# InkTime.net
KiCad netlist of a schematic drawn in EAGLE
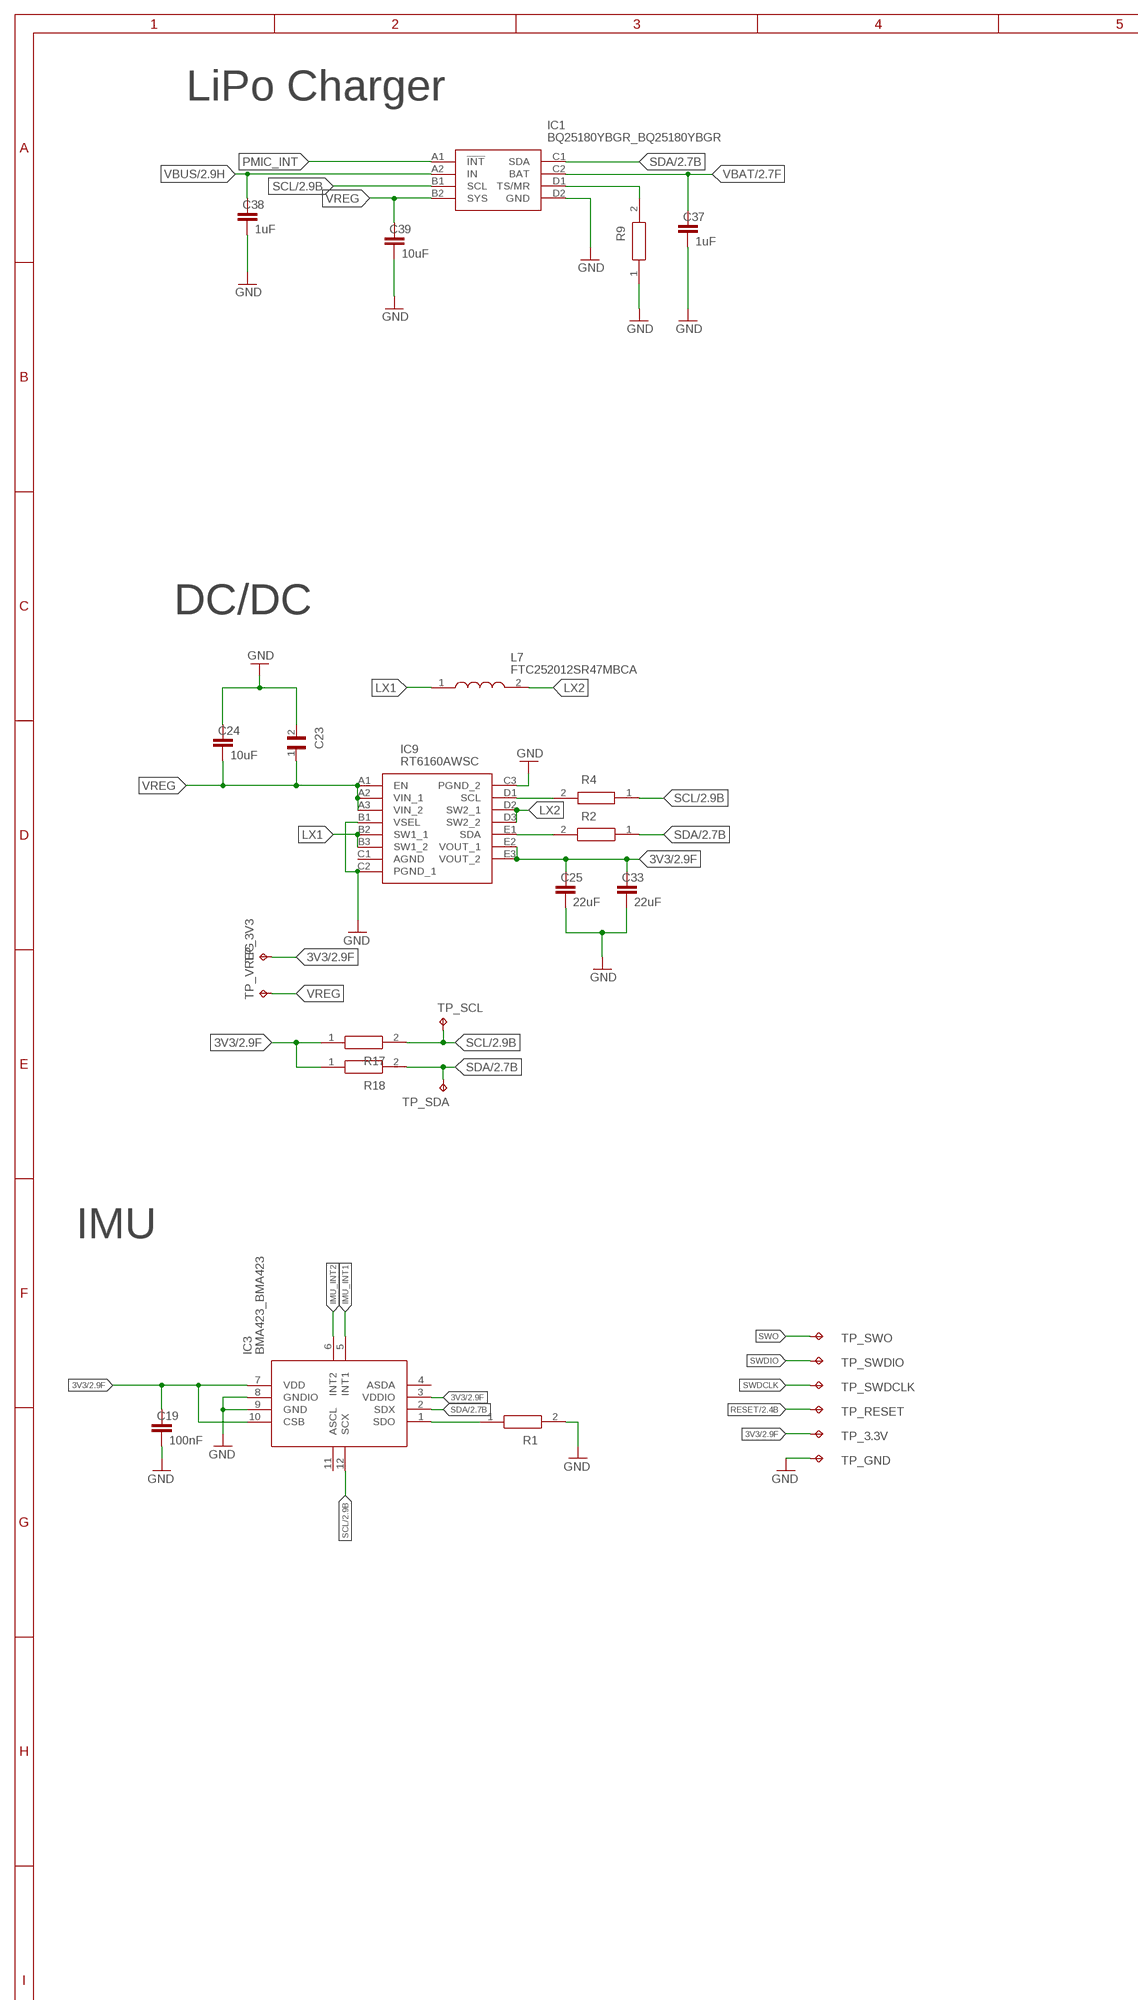
[diagram p0: schematic, sheet 1, part 1 of 2]
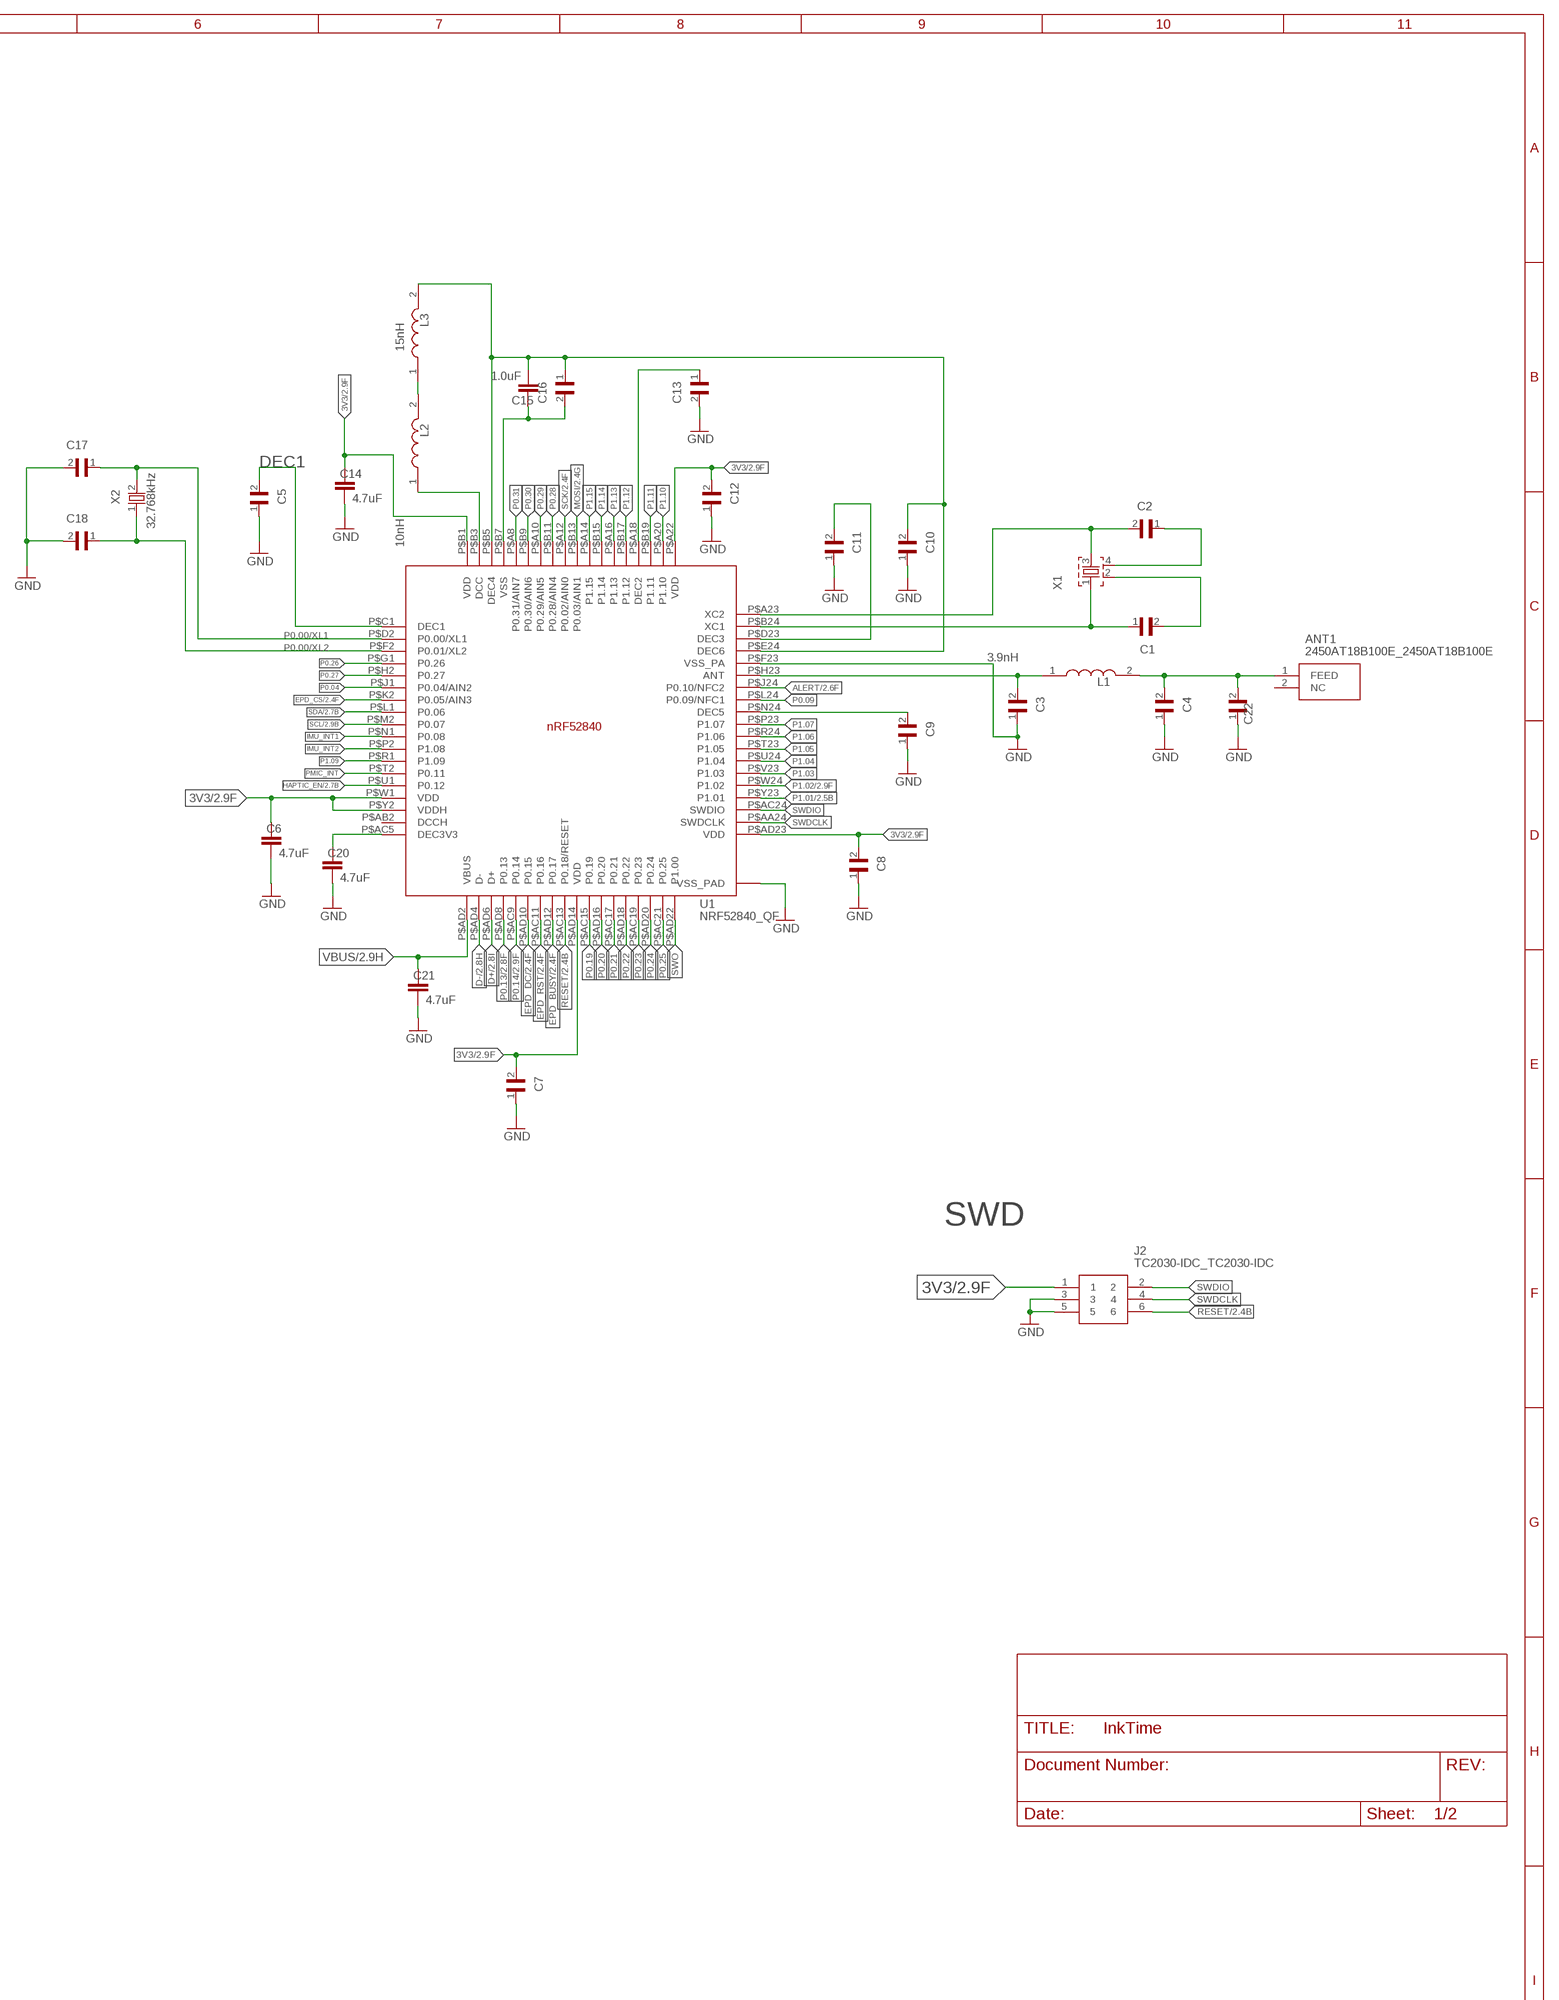
[diagram p1: schematic, sheet 1, part 2 of 2]
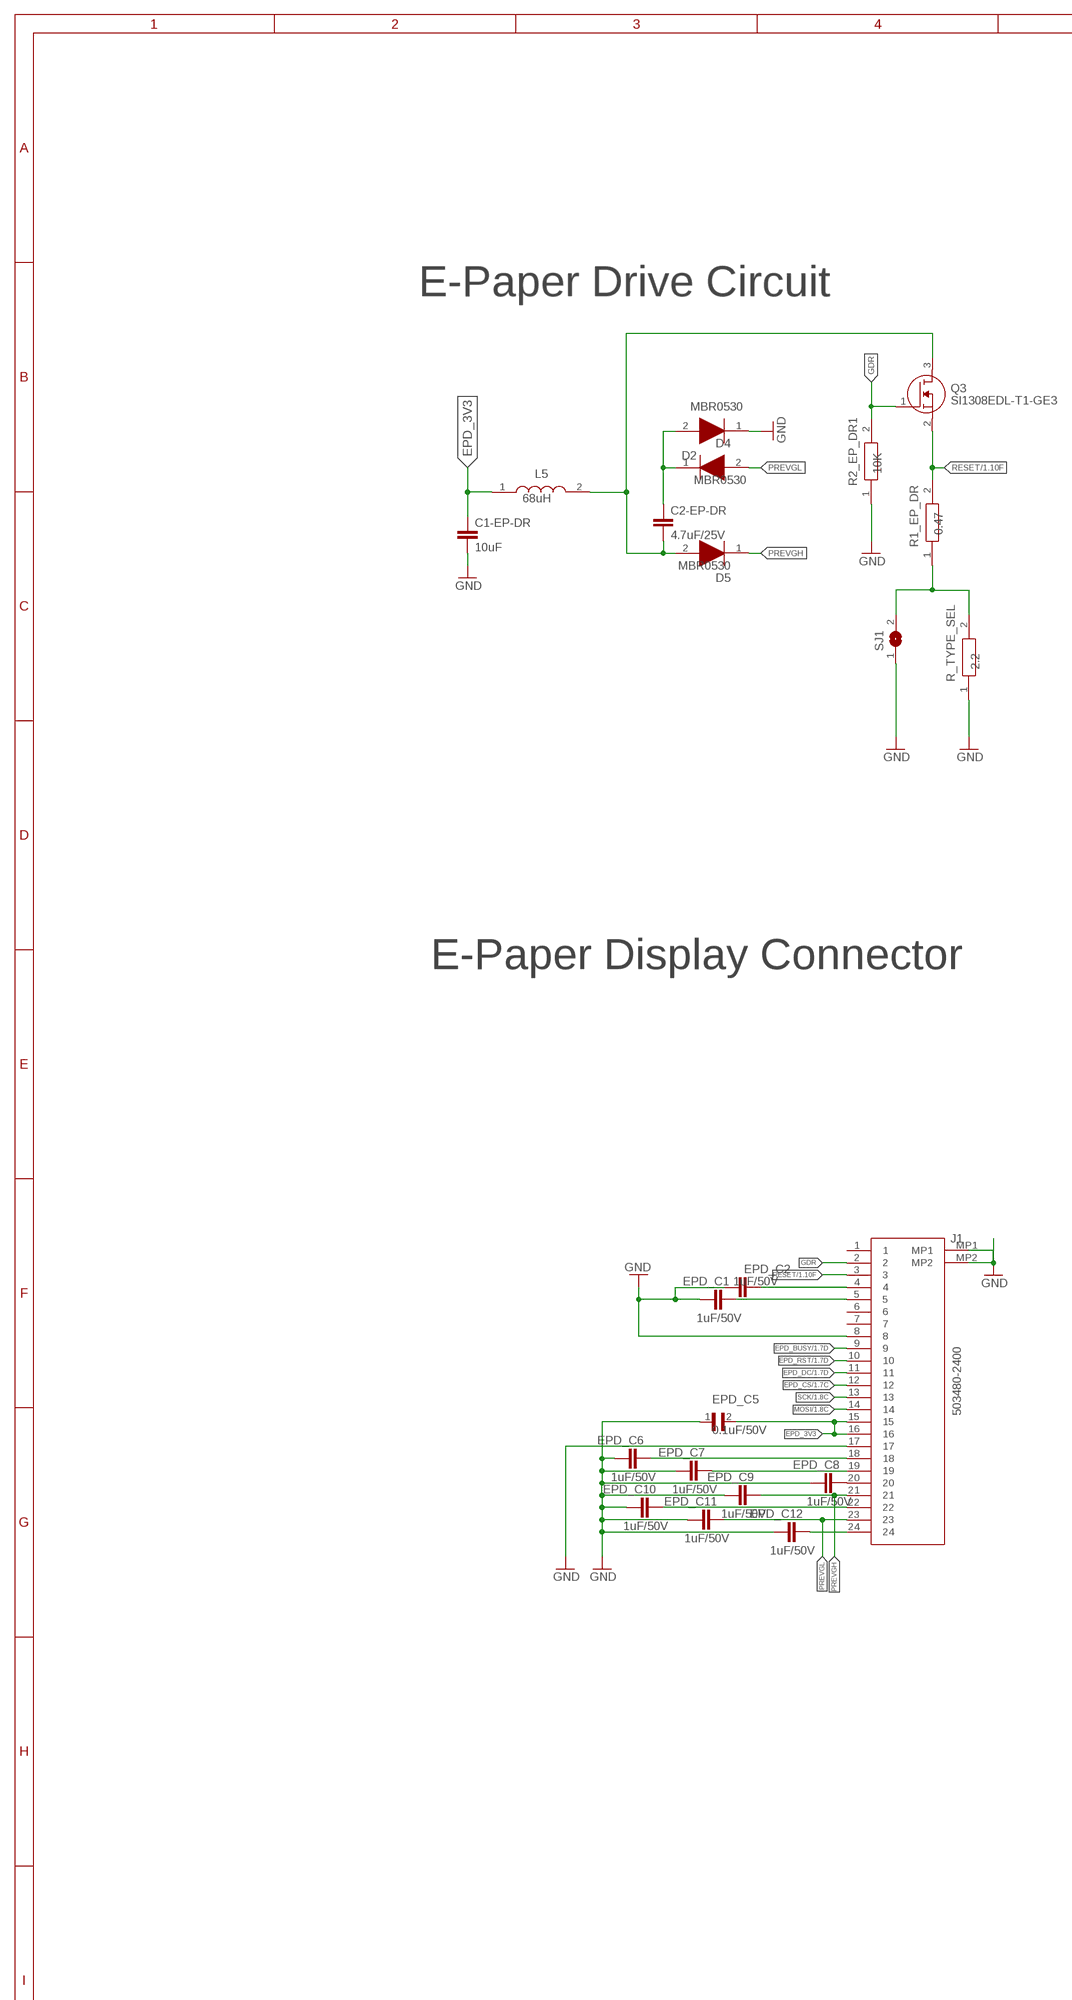
[diagram p2: schematic, sheet 2, part 1 of 2]
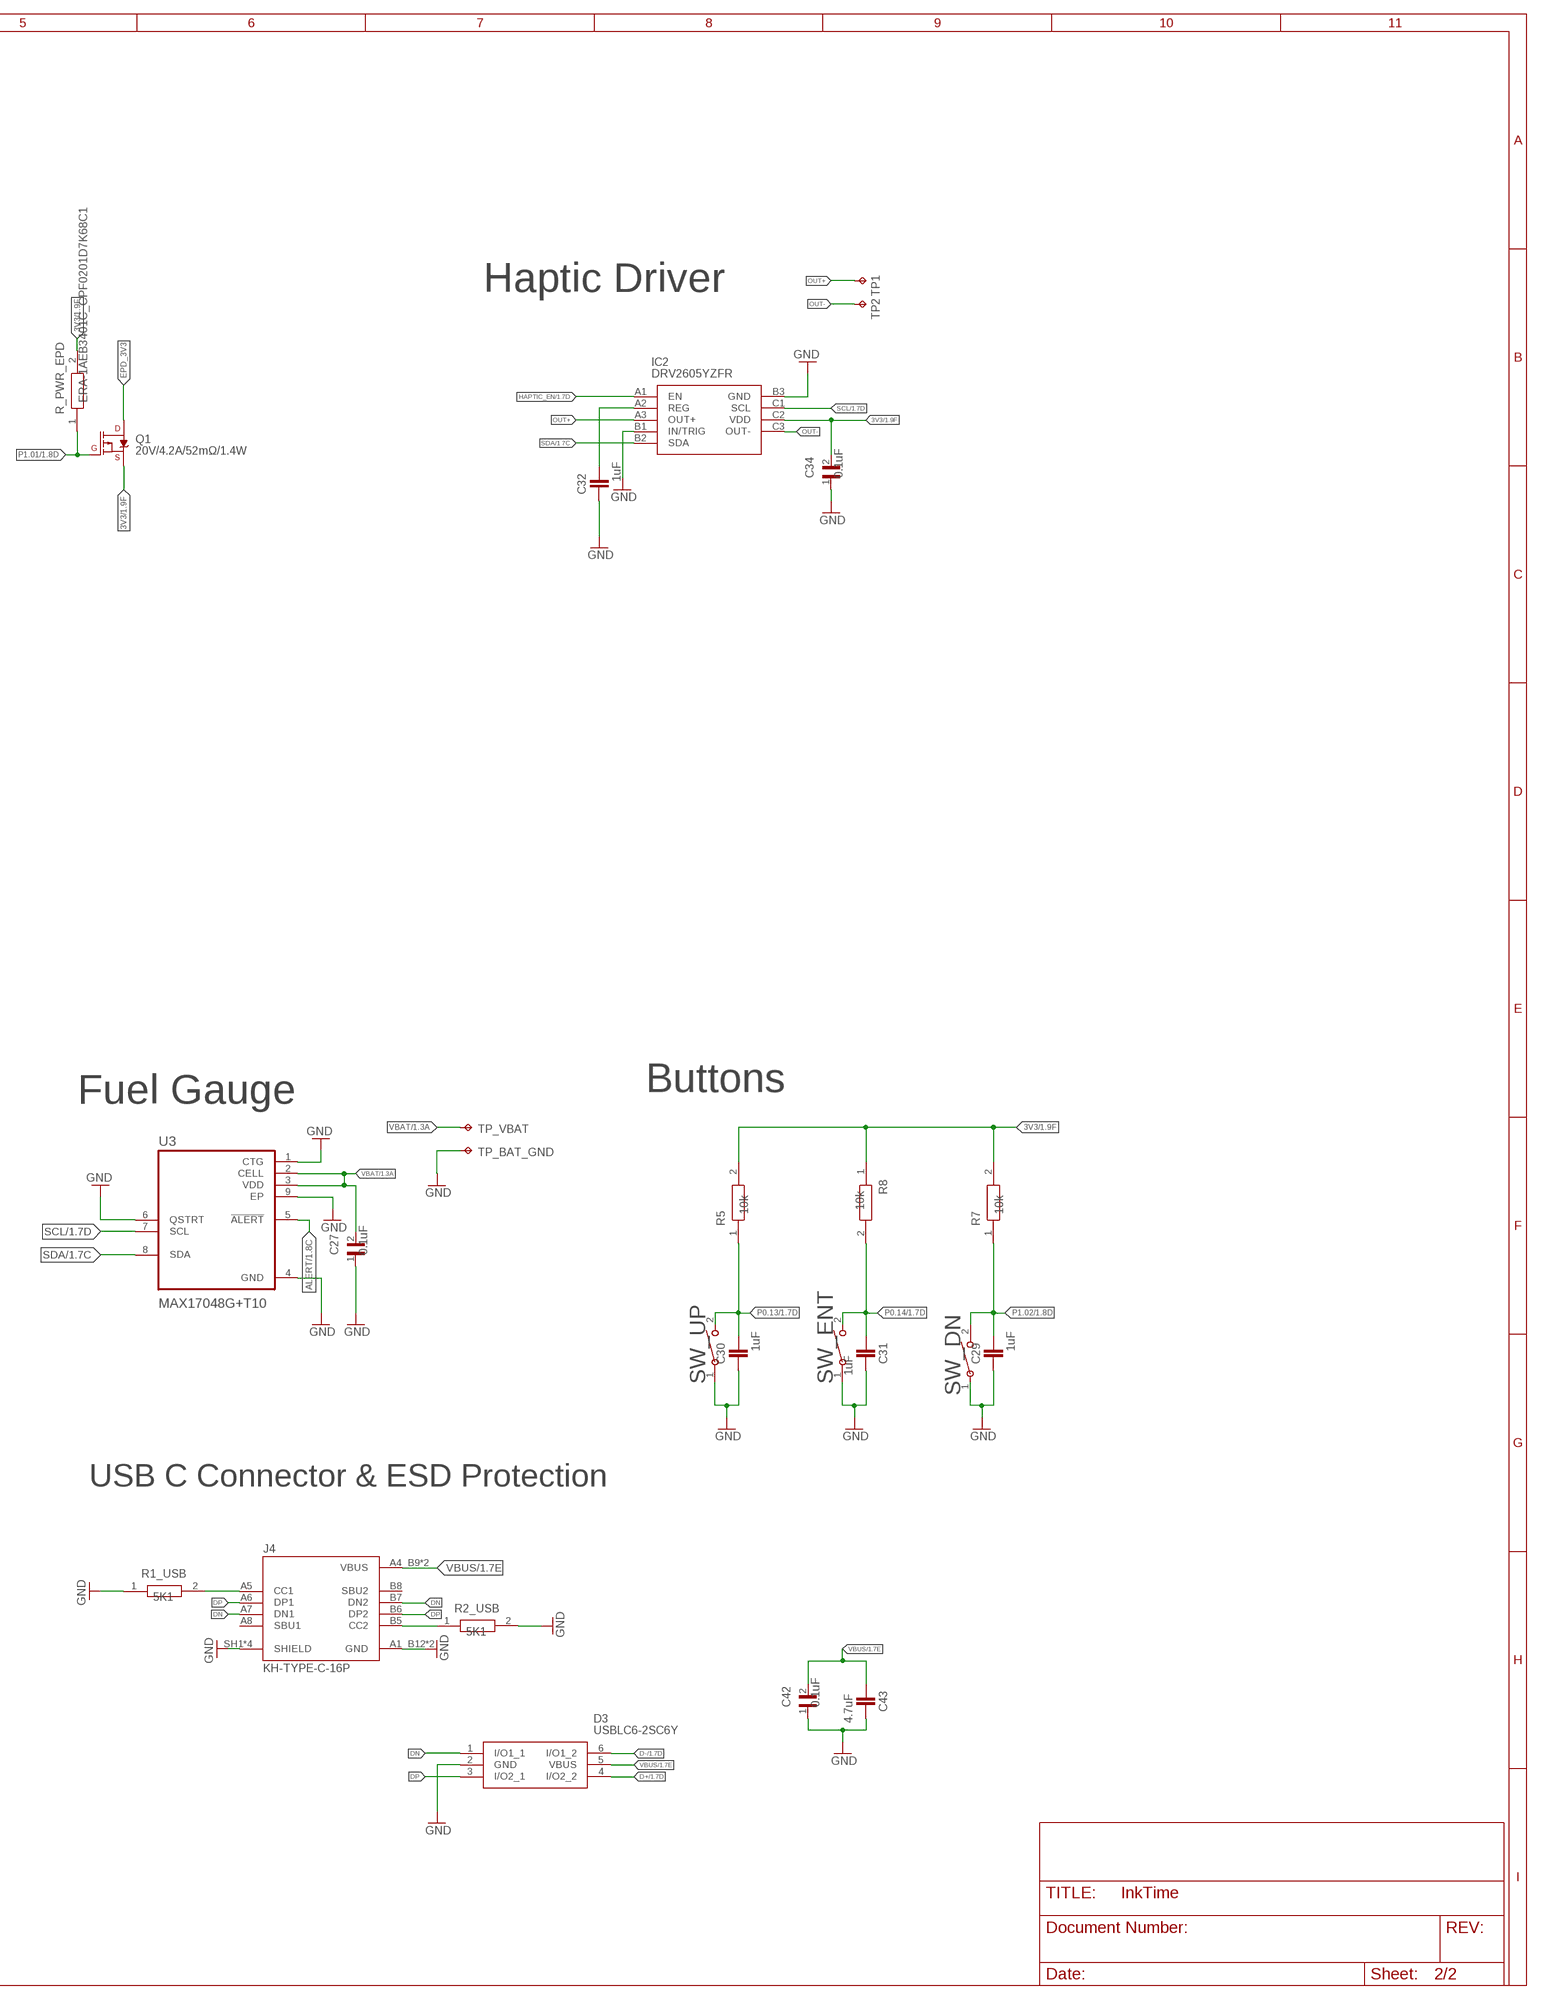
[diagram p3: schematic, sheet 2, part 2 of 2]

(export (version "E")
  (design (tool "Eeschema 10.0.6"))
  (components
    (comp (ref "C1-EP-DR")
      (value "10uF")
      (footprint "eagle-import:NORDIC_NRF_3_RESC0402_N")
      (libsource (lib "eagle-import") (part "NORDIC_NRF_3_CAPACITOR_0402_N"))
    )
    (comp (ref "C2-EP-DR")
      (value "4.7uF/25V")
      (footprint "eagle-import:NORDIC_NRF_3_RESC0402_N")
      (libsource (lib "eagle-import") (part "NORDIC_NRF_3_CAPACITOR_0402_N"))
    )
    (comp (ref "C27")
      (value "0.1uF")
      (footprint "eagle-import:GRM011R60J152KE01L_2_CAPC0201X13N")
      (fields (field (name "MF") "Murata") (field (name "MP") "GRM011R60J152KE01L"))
      (libsource (lib "eagle-import") (part "GRM011R60J152KE01L_2_GRM011R60J152KE01L"))
    )
    (comp (ref "C29")
      (value "1uF")
      (footprint "eagle-import:NORDIC_NRF_3_RESC0402_N")
      (libsource (lib "eagle-import") (part "NORDIC_NRF_3_CAPACITOR_0402_N"))
    )
    (comp (ref "C30")
      (value "1uF")
      (footprint "eagle-import:NORDIC_NRF_3_RESC0402_N")
      (libsource (lib "eagle-import") (part "NORDIC_NRF_3_CAPACITOR_0402_N"))
    )
    (comp (ref "C31")
      (value "1uF")
      (footprint "eagle-import:NORDIC_NRF_3_RESC0402_N")
      (libsource (lib "eagle-import") (part "NORDIC_NRF_3_CAPACITOR_0402_N"))
    )
    (comp (ref "C32")
      (value "1uF")
      (footprint "eagle-import:NORDIC_NRF_3_RESC0402_N")
      (libsource (lib "eagle-import") (part "NORDIC_NRF_3_CAPACITOR_0402_N"))
    )
    (comp (ref "C34")
      (value "0.1uF")
      (footprint "eagle-import:GRM011R60J152KE01L_2_CAPC0201X13N")
      (fields (field (name "MF") "Murata") (field (name "MP") "GRM011R60J152KE01L"))
      (libsource (lib "eagle-import") (part "GRM011R60J152KE01L_2_GRM011R60J152KE01L"))
    )
    (comp (ref "C42")
      (value "0.1uF")
      (footprint "eagle-import:GRM011R60J152KE01L_2_CAPC0201X13N")
      (fields (field (name "MF") "Murata") (field (name "MP") "GRM011R60J152KE01L"))
      (libsource (lib "eagle-import") (part "GRM011R60J152KE01L_2_GRM011R60J152KE01L"))
    )
    (comp (ref "C43")
      (value "4.7uF")
      (footprint "eagle-import:NORDIC_NRF_3_RESC0402_N")
      (libsource (lib "eagle-import") (part "NORDIC_NRF_3_CAPACITOR_0402_N"))
    )
    (comp (ref "D2")
      (value "MBR0530")
      (footprint "eagle-import:ESP32_C6_LIBRARY_5_SOD3716X135N")
      (fields (field (name "MF") "ON Semiconductor"))
      (libsource (lib "eagle-import") (part "ESP32_C6_LIBRARY_5_MBR0530"))
    )
    (comp (ref "D3")
      (value "USBLC6-2SC6Y")
      (footprint "eagle-import:ESP32_C6_LIBRARY_3_SOT95P280X145-6N")
      (fields (field (name "MF") "STMicroelectronics"))
      (libsource (lib "eagle-import") (part "ESP32_C6_LIBRARY_3_USBLC6-2SC6Y"))
    )
    (comp (ref "D4")
      (value "MBR0530")
      (footprint "eagle-import:ESP32_C6_LIBRARY_5_SOD3716X135N")
      (fields (field (name "MF") "ON Semiconductor"))
      (libsource (lib "eagle-import") (part "ESP32_C6_LIBRARY_5_MBR0530"))
    )
    (comp (ref "D5")
      (value "MBR0530")
      (footprint "eagle-import:ESP32_C6_LIBRARY_5_SOD3716X135N")
      (fields (field (name "MF") "ON Semiconductor"))
      (libsource (lib "eagle-import") (part "ESP32_C6_LIBRARY_5_MBR0530"))
    )
    (comp (ref "EPD_C1")
      (value "1uF/50V")
      (footprint "eagle-import:NORDIC_NRF_3_RESC0402_N")
      (libsource (lib "eagle-import") (part "NORDIC_NRF_3_CAPACITOR_0402_N"))
    )
    (comp (ref "EPD_C2")
      (value "1uF/50V")
      (footprint "eagle-import:NORDIC_NRF_3_RESC0402_N")
      (libsource (lib "eagle-import") (part "NORDIC_NRF_3_CAPACITOR_0402_N"))
    )
    (comp (ref "EPD_C5")
      (value "0.1uF/50V")
      (footprint "eagle-import:GRM011R60J152KE01L_2_CAPC0201X13N")
      (fields (field (name "MF") "Murata") (field (name "MP") "GRM011R60J152KE01L"))
      (libsource (lib "eagle-import") (part "GRM011R60J152KE01L_2_GRM011R60J152KE01L"))
    )
    (comp (ref "EPD_C6")
      (value "1uF/50V")
      (footprint "eagle-import:NORDIC_NRF_3_RESC0402_N")
      (libsource (lib "eagle-import") (part "NORDIC_NRF_3_CAPACITOR_0402_N"))
    )
    (comp (ref "EPD_C7")
      (value "1uF/50V")
      (footprint "eagle-import:NORDIC_NRF_3_RESC0402_N")
      (libsource (lib "eagle-import") (part "NORDIC_NRF_3_CAPACITOR_0402_N"))
    )
    (comp (ref "EPD_C8")
      (value "1uF/50V")
      (footprint "eagle-import:NORDIC_NRF_3_RESC0402_N")
      (libsource (lib "eagle-import") (part "NORDIC_NRF_3_CAPACITOR_0402_N"))
    )
    (comp (ref "EPD_C9")
      (value "1uF/50V")
      (footprint "eagle-import:NORDIC_NRF_3_RESC0402_N")
      (libsource (lib "eagle-import") (part "NORDIC_NRF_3_CAPACITOR_0402_N"))
    )
    (comp (ref "EPD_C10")
      (value "1uF/50V")
      (footprint "eagle-import:NORDIC_NRF_3_RESC0402_N")
      (libsource (lib "eagle-import") (part "NORDIC_NRF_3_CAPACITOR_0402_N"))
    )
    (comp (ref "EPD_C11")
      (value "1uF/50V")
      (footprint "eagle-import:NORDIC_NRF_3_RESC0402_N")
      (libsource (lib "eagle-import") (part "NORDIC_NRF_3_CAPACITOR_0402_N"))
    )
    (comp (ref "EPD_C12")
      (value "1uF/50V")
      (footprint "eagle-import:NORDIC_NRF_3_RESC0402_N")
      (libsource (lib "eagle-import") (part "NORDIC_NRF_3_CAPACITOR_0402_N"))
    )
    (comp (ref "IC2")
      (value "DRV2605YZFR")
      (footprint "eagle-import:DRV2605YZFR_BGA9C50P3X3_144X144X62")
      (libsource (lib "eagle-import") (part "DRV2605YZFR_DRV2605YZFR"))
    )
    (comp (ref "J1")
      (value "503480-2400")
      (footprint "eagle-import:503480-2400_5034802400")
      (fields (field (name "MOUSER_PART_NUMBER") "538-503480-2400"))
      (libsource (lib "eagle-import") (part "503480-2400_503480-2400"))
    )
    (comp (ref "J4")
      (value "KH-TYPE-C-16P")
      (footprint "eagle-import:KH-TYPE-C-16P_KINGHELM_KH-TYPE-C-16P")
      (fields (field (name "MF") "kinghelm"))
      (libsource (lib "eagle-import") (part "KH-TYPE-C-16P_KH-TYPE-C-16P"))
    )
    (comp (ref "L5")
      (value "68uH")
      (footprint "eagle-import:MLP2016SR47MT0S1_INDC2016X100N")
      (fields (field (name "MANUFACTURER_PART_NUMBER") "FTC252012SR47MBCA"))
      (libsource (lib "eagle-import") (part "MLP2016SR47MT0S1_FTC252012SR47MBCA"))
    )
    (comp (ref "Q1")
      (value "20V/4.2A/52mΩ/1.4W")
      (footprint "eagle-import:ESP32_C6_LIBRARY_4_ESP32_C6_LIBRARY_4_ESP32_C6_LIBRARY_4_ESP32_C6_LIBRARY_4_ESP32_WROVER_SPARKFUN-DISCRETESEMI_SOT23-3")
      (libsource (lib "eagle-import") (part "ESP32_C6_LIBRARY_4_ESP32_WROVER_SPARKFUN-DISCRETESEMI_MOSFET_PCH-DMG2305UX-7"))
    )
    (comp (ref "Q3")
      (value "SI1308EDL-T1-GE3")
      (footprint "eagle-import:ESP32_C6_LIBRARY_6_SOT65P210X110-3N")
      (fields (field (name "MF") "Vishay Siliconix"))
      (libsource (lib "eagle-import") (part "ESP32_C6_LIBRARY_6_SI1308EDL-T1-GE3"))
    )
    (comp (ref "R1_EP_DR")
      (value "0.47")
      (footprint "eagle-import:ERA-1AEB3401C_0201")
      (libsource (lib "eagle-import") (part "ERA-1AEB3401C_CPF0201D7K68C1"))
    )
    (comp (ref "R1_USB")
      (value "5K1")
      (footprint "eagle-import:ERA-1AEB3401C_0201")
      (libsource (lib "eagle-import") (part "ERA-1AEB3401C_CPF0201D7K68C1"))
    )
    (comp (ref "R2_EP_DR1")
      (value "10K")
      (footprint "eagle-import:ERA-1AEB3401C_0201")
      (libsource (lib "eagle-import") (part "ERA-1AEB3401C_CPF0201D7K68C1"))
    )
    (comp (ref "R2_USB")
      (value "5K1")
      (footprint "eagle-import:ERA-1AEB3401C_0201")
      (libsource (lib "eagle-import") (part "ERA-1AEB3401C_CPF0201D7K68C1"))
    )
    (comp (ref "R5")
      (value "10k")
      (footprint "eagle-import:ERA-1AEB3401C_0201")
      (libsource (lib "eagle-import") (part "ERA-1AEB3401C_CPF0201D7K68C1"))
    )
    (comp (ref "R7")
      (value "10k")
      (footprint "eagle-import:ERA-1AEB3401C_0201")
      (libsource (lib "eagle-import") (part "ERA-1AEB3401C_CPF0201D7K68C1"))
    )
    (comp (ref "R8")
      (value "10k")
      (footprint "eagle-import:ERA-1AEB3401C_0201")
      (libsource (lib "eagle-import") (part "ERA-1AEB3401C_CPF0201D7K68C1"))
    )
    (comp (ref "R_PWR_EPD")
      (value "ERA-1AEB3401C_CPF0201D7K68C1")
      (footprint "eagle-import:ERA-1AEB3401C_0201")
      (libsource (lib "eagle-import") (part "ERA-1AEB3401C_CPF0201D7K68C1"))
    )
    (comp (ref "R_TYPE_SEL")
      (value "2.2")
      (footprint "eagle-import:ERA-1AEB3401C_0201")
      (libsource (lib "eagle-import") (part "ERA-1AEB3401C_CPF0201D7K68C1"))
    )
    (comp (ref "SJ1")
      (value "ESP32_C6_LIBRARY_7_JUMPER_SJ")
      (footprint "eagle-import:ESP32_C6_LIBRARY_7_JUMPER_SJ")
      (libsource (lib "eagle-import") (part "ESP32_C6_LIBRARY_7_JUMPER_SJ"))
    )
    (comp (ref "SW_DN")
      (value "2025-10-22_07-23-44_LIBRARY_EVP-AKE31ASW_EVP-AKE31A_PAN")
      (footprint "eagle-import:2025-10-22_07-23-44_LIBRARY_SW_EVP-AKE31A_PAN")
      (fields
        (field (name "MANUFACTURER_PART_NUMBER") "EVP-AKE31A")
        (field (name "COPYRIGHT") "Copyright (C) 2025 Ultra Librarian. All rights reserved.")
      )
      (libsource (lib "eagle-import") (part "2025-10-22_07-23-44_LIBRARY_EVP-AKE31ASW_EVP-AKE31A_PAN"))
    )
    (comp (ref "SW_ENT")
      (value "2025-10-22_07-23-44_LIBRARY_EVP-AKE31ASW_EVP-AKE31A_PAN")
      (footprint "eagle-import:2025-10-22_07-23-44_LIBRARY_SW_EVP-AKE31A_PAN")
      (fields
        (field (name "MANUFACTURER_PART_NUMBER") "EVP-AKE31A")
        (field (name "COPYRIGHT") "Copyright (C) 2025 Ultra Librarian. All rights reserved.")
      )
      (libsource (lib "eagle-import") (part "2025-10-22_07-23-44_LIBRARY_EVP-AKE31ASW_EVP-AKE31A_PAN"))
    )
    (comp (ref "SW_UP")
      (value "2025-10-22_07-23-44_LIBRARY_EVP-AKE31ASW_EVP-AKE31A_PAN")
      (footprint "eagle-import:2025-10-22_07-23-44_LIBRARY_SW_EVP-AKE31A_PAN")
      (fields
        (field (name "MANUFACTURER_PART_NUMBER") "EVP-AKE31A")
        (field (name "COPYRIGHT") "Copyright (C) 2025 Ultra Librarian. All rights reserved.")
      )
      (libsource (lib "eagle-import") (part "2025-10-22_07-23-44_LIBRARY_EVP-AKE31ASW_EVP-AKE31A_PAN"))
    )
    (comp (ref "TP1")
      (value "HECTOR_WATCH_1_TPTP20R")
      (footprint "eagle-import:HECTOR_WATCH_1_TP20R")
      (libsource (lib "eagle-import") (part "HECTOR_WATCH_1_TPTP20R"))
    )
    (comp (ref "TP2")
      (value "HECTOR_WATCH_1_TPTP20R")
      (footprint "eagle-import:HECTOR_WATCH_1_TP20R")
      (libsource (lib "eagle-import") (part "HECTOR_WATCH_1_TPTP20R"))
    )
    (comp (ref "TP_BAT_GND")
      (value "HECTOR_WATCH_1_TPTP20R")
      (footprint "eagle-import:HECTOR_WATCH_1_TP20R")
      (libsource (lib "eagle-import") (part "HECTOR_WATCH_1_TPTP20R"))
    )
    (comp (ref "TP_VBAT")
      (value "HECTOR_WATCH_1_TPTP20R")
      (footprint "eagle-import:HECTOR_WATCH_1_TP20R")
      (libsource (lib "eagle-import") (part "HECTOR_WATCH_1_TPTP20R"))
    )
    (comp (ref "U3")
      (value "MAX17048G+T10")
      (footprint "eagle-import:ESP32_C6_LIBRARY_SON50P200X200X80-9N")
      (fields (field (name "MF") "Analog Devices"))
      (libsource (lib "eagle-import") (part "ESP32_C6_LIBRARY_MAX17048G+T10"))
    )
    (comp (ref "ANT1")
      (value "2450AT18B100E_2450AT18B100E")
      (footprint "eagle-import:2450AT18B100E_ANTC3216X140N")
      (fields
        (field (name "ARROW_PART_NUMBER") "2450AT18B100E")
        (field (name "MOUSER_PART_NUMBER") "609-2450AT18B100E")
      )
      (libsource (lib "eagle-import") (part "2450AT18B100E_2450AT18B100E"))
    )
    (comp (ref "C1")
      (value "12pF")
      (footprint "eagle-import:GRM011R60J152KE01L_2_CAPC0201X13N")
      (fields (field (name "MF") "Murata") (field (name "MP") "GRM011R60J152KE01L"))
      (libsource (lib "eagle-import") (part "GRM011R60J152KE01L_2_GRM011R60J152KE01L"))
    )
    (comp (ref "C2")
      (value "12pF")
      (footprint "eagle-import:GRM011R60J152KE01L_2_CAPC0201X13N")
      (fields (field (name "MF") "Murata") (field (name "MP") "GRM011R60J152KE01L"))
      (libsource (lib "eagle-import") (part "GRM011R60J152KE01L_2_GRM011R60J152KE01L"))
    )
    (comp (ref "C3")
      (value "1pF")
      (footprint "eagle-import:GRM011R60J152KE01L_2_CAPC0201X13N")
      (fields (field (name "MF") "Murata") (field (name "MP") "GRM011R60J152KE01L"))
      (libsource (lib "eagle-import") (part "GRM011R60J152KE01L_2_GRM011R60J152KE01L"))
    )
    (comp (ref "C4")
      (value "1pF")
      (footprint "eagle-import:GRM011R60J152KE01L_2_CAPC0201X13N")
      (fields (field (name "MF") "Murata") (field (name "MP") "GRM011R60J152KE01L"))
      (libsource (lib "eagle-import") (part "GRM011R60J152KE01L_2_GRM011R60J152KE01L"))
    )
    (comp (ref "C5")
      (value "100nF")
      (footprint "eagle-import:GRM011R60J152KE01L_2_CAPC0201X13N")
      (fields (field (name "MF") "Murata") (field (name "MP") "GRM011R60J152KE01L"))
      (libsource (lib "eagle-import") (part "GRM011R60J152KE01L_2_GRM011R60J152KE01L"))
    )
    (comp (ref "C6")
      (value "4.7uF")
      (footprint "eagle-import:NORDIC_NRF_3_RESC0402_N")
      (libsource (lib "eagle-import") (part "NORDIC_NRF_3_CAPACITOR_0402_N"))
    )
    (comp (ref "C7")
      (value "100nF")
      (footprint "eagle-import:GRM011R60J152KE01L_2_CAPC0201X13N")
      (fields (field (name "MF") "Murata") (field (name "MP") "GRM011R60J152KE01L"))
      (libsource (lib "eagle-import") (part "GRM011R60J152KE01L_2_GRM011R60J152KE01L"))
    )
    (comp (ref "C8")
      (value "100nF")
      (footprint "eagle-import:GRM011R60J152KE01L_2_CAPC0201X13N")
      (fields (field (name "MF") "Murata") (field (name "MP") "GRM011R60J152KE01L"))
      (libsource (lib "eagle-import") (part "GRM011R60J152KE01L_2_GRM011R60J152KE01L"))
    )
    (comp (ref "C9")
      (value "820pF")
      (footprint "eagle-import:GRM011R60J152KE01L_2_CAPC0201X13N")
      (fields (field (name "MF") "Murata") (field (name "MP") "GRM011R60J152KE01L"))
      (libsource (lib "eagle-import") (part "GRM011R60J152KE01L_2_GRM011R60J152KE01L"))
    )
    (comp (ref "C10")
      (value "N.C.")
      (footprint "eagle-import:GRM011R60J152KE01L_2_CAPC0201X13N")
      (fields (field (name "MF") "Murata") (field (name "MP") "GRM011R60J152KE01L"))
      (libsource (lib "eagle-import") (part "GRM011R60J152KE01L_2_GRM011R60J152KE01L"))
    )
    (comp (ref "C11")
      (value "100pF")
      (footprint "eagle-import:GRM011R60J152KE01L_2_CAPC0201X13N")
      (fields (field (name "MF") "Murata") (field (name "MP") "GRM011R60J152KE01L"))
      (libsource (lib "eagle-import") (part "GRM011R60J152KE01L_2_GRM011R60J152KE01L"))
    )
    (comp (ref "C12")
      (value "100nF")
      (footprint "eagle-import:GRM011R60J152KE01L_2_CAPC0201X13N")
      (fields (field (name "MF") "Murata") (field (name "MP") "GRM011R60J152KE01L"))
      (libsource (lib "eagle-import") (part "GRM011R60J152KE01L_2_GRM011R60J152KE01L"))
    )
    (comp (ref "C13")
      (value "N.C.")
      (footprint "eagle-import:GRM011R60J152KE01L_2_CAPC0201X13N")
      (fields (field (name "MF") "Murata") (field (name "MP") "GRM011R60J152KE01L"))
      (libsource (lib "eagle-import") (part "GRM011R60J152KE01L_2_GRM011R60J152KE01L"))
    )
    (comp (ref "C14")
      (value "4.7uF")
      (footprint "eagle-import:NORDIC_NRF_3_RESC0402_N")
      (libsource (lib "eagle-import") (part "NORDIC_NRF_3_CAPACITOR_0402_N"))
    )
    (comp (ref "C15")
      (value "1.0uF")
      (footprint "eagle-import:NORDIC_NRF_3_RESC0402_N")
      (libsource (lib "eagle-import") (part "NORDIC_NRF_3_CAPACITOR_0402_N"))
    )
    (comp (ref "C16")
      (value "47nF")
      (footprint "eagle-import:GRM011R60J152KE01L_2_CAPC0201X13N")
      (fields (field (name "MF") "Murata") (field (name "MP") "GRM011R60J152KE01L"))
      (libsource (lib "eagle-import") (part "GRM011R60J152KE01L_2_GRM011R60J152KE01L"))
    )
    (comp (ref "C17")
      (value "12pF")
      (footprint "eagle-import:GRM011R60J152KE01L_2_CAPC0201X13N")
      (fields (field (name "MF") "Murata") (field (name "MP") "GRM011R60J152KE01L"))
      (libsource (lib "eagle-import") (part "GRM011R60J152KE01L_2_GRM011R60J152KE01L"))
    )
    (comp (ref "C18")
      (value "12pF")
      (footprint "eagle-import:GRM011R60J152KE01L_2_CAPC0201X13N")
      (fields (field (name "MF") "Murata") (field (name "MP") "GRM011R60J152KE01L"))
      (libsource (lib "eagle-import") (part "GRM011R60J152KE01L_2_GRM011R60J152KE01L"))
    )
    (comp (ref "C19")
      (value "100nF")
      (footprint "eagle-import:NORDIC_NRF_3_RESC0402_N")
      (libsource (lib "eagle-import") (part "NORDIC_NRF_3_CAPACITOR_0402_N"))
    )
    (comp (ref "C20")
      (value "4.7uF")
      (footprint "eagle-import:NORDIC_NRF_3_RESC0402_N")
      (libsource (lib "eagle-import") (part "NORDIC_NRF_3_CAPACITOR_0402_N"))
    )
    (comp (ref "C21")
      (value "4.7uF")
      (footprint "eagle-import:NORDIC_NRF_3_RESC0402_N")
      (libsource (lib "eagle-import") (part "NORDIC_NRF_3_CAPACITOR_0402_N"))
    )
    (comp (ref "C22")
      (value "N.C.")
      (footprint "eagle-import:GRM011R60J152KE01L_2_CAPC0201X13N")
      (fields (field (name "MF") "Murata") (field (name "MP") "GRM011R60J152KE01L"))
      (libsource (lib "eagle-import") (part "GRM011R60J152KE01L_2_GRM011R60J152KE01L"))
    )
    (comp (ref "C23")
      (value "0.1uF")
      (footprint "eagle-import:GRM011R60J152KE01L_2_CAPC0201X13N")
      (fields (field (name "MF") "Murata") (field (name "MP") "GRM011R60J152KE01L"))
      (libsource (lib "eagle-import") (part "GRM011R60J152KE01L_2_GRM011R60J152KE01L"))
    )
    (comp (ref "C24")
      (value "10uF")
      (footprint "eagle-import:NORDIC_NRF_3_RESC0402_N")
      (libsource (lib "eagle-import") (part "NORDIC_NRF_3_CAPACITOR_0402_N"))
    )
    (comp (ref "C25")
      (value "22uF")
      (footprint "eagle-import:NORDIC_NRF_3_RESC0402_N")
      (libsource (lib "eagle-import") (part "NORDIC_NRF_3_CAPACITOR_0402_N"))
    )
    (comp (ref "C33")
      (value "22uF")
      (footprint "eagle-import:NORDIC_NRF_3_RESC0402_N")
      (libsource (lib "eagle-import") (part "NORDIC_NRF_3_CAPACITOR_0402_N"))
    )
    (comp (ref "C37")
      (value "1uF")
      (footprint "eagle-import:NORDIC_NRF_3_RESC0402_N")
      (libsource (lib "eagle-import") (part "NORDIC_NRF_3_CAPACITOR_0402_N"))
    )
    (comp (ref "C38")
      (value "1uF")
      (footprint "eagle-import:NORDIC_NRF_3_RESC0402_N")
      (libsource (lib "eagle-import") (part "NORDIC_NRF_3_CAPACITOR_0402_N"))
    )
    (comp (ref "C39")
      (value "10uF")
      (footprint "eagle-import:NORDIC_NRF_3_RESC0402_N")
      (libsource (lib "eagle-import") (part "NORDIC_NRF_3_CAPACITOR_0402_N"))
    )
    (comp (ref "IC1")
      (value "BQ25180YBGR_BQ25180YBGR")
      (footprint "eagle-import:BQ25180YBGR_BGA8C40P2X4_100X155X50")
      (fields
        (field (name "ARROW_PART_NUMBER") "BQ25180YBGR")
        (field (name "MOUSER_PART_NUMBER") "595-BQ25180YBGR")
      )
      (libsource (lib "eagle-import") (part "BQ25180YBGR_BQ25180YBGR"))
    )
    (comp (ref "IC3")
      (value "BMA423_BMA423")
      (footprint "eagle-import:BMA423_BMA423")
      (fields (field (name "ARROW_PART_NUMBER") "BMA423") (field (name "MOUSER_PART_NUMBER") "262-BMA423"))
      (libsource (lib "eagle-import") (part "BMA423_BMA423"))
    )
    (comp (ref "IC9")
      (value "RT6160AWSC")
      (footprint "eagle-import:RT6160AWSC_BGA15C40P3X5_140X230X60")
      (fields (field (name "MOUSER_PART_NUMBER") "835-RT6160AWSC"))
      (libsource (lib "eagle-import") (part "RT6160AWSC_RT6160AWSC"))
    )
    (comp (ref "J2")
      (value "TC2030-IDC_TC2030-IDC")
      (footprint "eagle-import:TC2030-IDC_TC2030IDC")
      (fields (field (name "MANUFACTURER_PART_NUMBER") "TC2030-IDC"))
      (libsource (lib "eagle-import") (part "TC2030-IDC_TC2030-IDC"))
    )
    (comp (ref "L1")
      (value "3.9nH")
      (footprint "eagle-import:MLP2016SR47MT0S1_INDC2016X100N")
      (fields (field (name "MANUFACTURER_PART_NUMBER") "FTC252012SR47MBCA"))
      (libsource (lib "eagle-import") (part "MLP2016SR47MT0S1_FTC252012SR47MBCA"))
    )
    (comp (ref "L2")
      (value "10nH")
      (footprint "eagle-import:MLP2016SR47MT0S1_INDC2016X100N")
      (fields (field (name "MANUFACTURER_PART_NUMBER") "FTC252012SR47MBCA"))
      (libsource (lib "eagle-import") (part "MLP2016SR47MT0S1_FTC252012SR47MBCA"))
    )
    (comp (ref "L3")
      (value "15nH")
      (footprint "eagle-import:MLP2016SR47MT0S1_INDC2016X100N")
      (fields (field (name "MANUFACTURER_PART_NUMBER") "FTC252012SR47MBCA"))
      (libsource (lib "eagle-import") (part "MLP2016SR47MT0S1_FTC252012SR47MBCA"))
    )
    (comp (ref "L7")
      (value "FTC252012SR47MBCA")
      (footprint "eagle-import:MLP2016SR47MT0S1_INDC2016X100N")
      (libsource (lib "eagle-import") (part "MLP2016SR47MT0S1_FTC252012SR47MBCA"))
    )
    (comp (ref "R1")
      (value "0")
      (footprint "eagle-import:ERA-1AEB3401C_0201")
      (libsource (lib "eagle-import") (part "ERA-1AEB3401C_CPF0201D7K68C1"))
    )
    (comp (ref "R2")
      (value "0")
      (footprint "eagle-import:ERA-1AEB3401C_0201")
      (libsource (lib "eagle-import") (part "ERA-1AEB3401C_CPF0201D7K68C1"))
    )
    (comp (ref "R4")
      (value "0")
      (footprint "eagle-import:ERA-1AEB3401C_0201")
      (libsource (lib "eagle-import") (part "ERA-1AEB3401C_CPF0201D7K68C1"))
    )
    (comp (ref "R9")
      (value "10k")
      (footprint "eagle-import:ERA-1AEB3401C_0201")
      (libsource (lib "eagle-import") (part "ERA-1AEB3401C_CPF0201D7K68C1"))
    )
    (comp (ref "R17")
      (value "3k3")
      (footprint "eagle-import:ERA-1AEB3401C_0201")
      (libsource (lib "eagle-import") (part "ERA-1AEB3401C_CPF0201D7K68C1"))
    )
    (comp (ref "R18")
      (value "3K3")
      (footprint "eagle-import:ERA-1AEB3401C_0201")
      (libsource (lib "eagle-import") (part "ERA-1AEB3401C_CPF0201D7K68C1"))
    )
    (comp (ref "TP_3.3V")
      (value "HECTOR_WATCH_1_TPTP20R")
      (footprint "eagle-import:HECTOR_WATCH_1_TP20R")
      (libsource (lib "eagle-import") (part "HECTOR_WATCH_1_TPTP20R"))
    )
    (comp (ref "TP_3V3")
      (value "HECTOR_WATCH_1_TPTP20R")
      (footprint "eagle-import:HECTOR_WATCH_1_TP20R")
      (libsource (lib "eagle-import") (part "HECTOR_WATCH_1_TPTP20R"))
    )
    (comp (ref "TP_GND")
      (value "HECTOR_WATCH_1_TPTP20R")
      (footprint "eagle-import:HECTOR_WATCH_1_TP20R")
      (libsource (lib "eagle-import") (part "HECTOR_WATCH_1_TPTP20R"))
    )
    (comp (ref "TP_RESET")
      (value "HECTOR_WATCH_1_TPTP20R")
      (footprint "eagle-import:HECTOR_WATCH_1_TP20R")
      (libsource (lib "eagle-import") (part "HECTOR_WATCH_1_TPTP20R"))
    )
    (comp (ref "TP_SCL")
      (value "HECTOR_WATCH_1_TPTP20R")
      (footprint "eagle-import:HECTOR_WATCH_1_TP20R")
      (libsource (lib "eagle-import") (part "HECTOR_WATCH_1_TPTP20R"))
    )
    (comp (ref "TP_SDA")
      (value "HECTOR_WATCH_1_TPTP20R")
      (footprint "eagle-import:HECTOR_WATCH_1_TP20R")
      (libsource (lib "eagle-import") (part "HECTOR_WATCH_1_TPTP20R"))
    )
    (comp (ref "TP_SWDCLK")
      (value "HECTOR_WATCH_1_TPTP20R")
      (footprint "eagle-import:HECTOR_WATCH_1_TP20R")
      (libsource (lib "eagle-import") (part "HECTOR_WATCH_1_TPTP20R"))
    )
    (comp (ref "TP_SWDIO")
      (value "HECTOR_WATCH_1_TPTP20R")
      (footprint "eagle-import:HECTOR_WATCH_1_TP20R")
      (libsource (lib "eagle-import") (part "HECTOR_WATCH_1_TPTP20R"))
    )
    (comp (ref "TP_SWO")
      (value "HECTOR_WATCH_1_TPTP20R")
      (footprint "eagle-import:HECTOR_WATCH_1_TP20R")
      (libsource (lib "eagle-import") (part "HECTOR_WATCH_1_TPTP20R"))
    )
    (comp (ref "TP_VREG")
      (value "HECTOR_WATCH_1_TPTP20R")
      (footprint "eagle-import:HECTOR_WATCH_1_TP20R")
      (libsource (lib "eagle-import") (part "HECTOR_WATCH_1_TPTP20R"))
    )
    (comp (ref "U1")
      (value "NRF52840_QF")
      (footprint "eagle-import:NORDIC_NRF_4_AQFN50P700X700X85_HS-74N")
      (libsource (lib "eagle-import") (part "NORDIC_NRF_4_NRF52840_QF"))
    )
    (comp (ref "X1")
      (value "NORDIC_NRF_XTAL_32MHZ")
      (footprint "eagle-import:NORDIC_NRF_BT-XTAL_2016_N")
      (libsource (lib "eagle-import") (part "NORDIC_NRF_XTAL_32MHZ"))
    )
    (comp (ref "X2")
      (value "32.768kHz")
      (footprint "eagle-import:NORDIC_NRF_1_XTAL_3215_N")
      (libsource (lib "eagle-import") (part "NORDIC_NRF_1_XTAL_32KHZ"))
    )
  )
  (nets
    (net (code "1") (name "3V3") (class "Default")
      (node (ref "C12") (pin "2") (pinfunction "2_2") (pintype "passive"))
      (node (ref "C14") (pin "1") (pinfunction "1_1") (pintype "passive"))
      (node (ref "C19") (pin "1") (pinfunction "1_1") (pintype "passive"))
      (node (ref "C25") (pin "1") (pinfunction "1_1") (pintype "passive"))
      (node (ref "C33") (pin "1") (pinfunction "1_1") (pintype "passive"))
      (node (ref "C34") (pin "2") (pinfunction "2_2") (pintype "passive"))
      (node (ref "C6") (pin "1") (pinfunction "1_1") (pintype "passive"))
      (node (ref "C7") (pin "2") (pinfunction "2_2") (pintype "passive"))
      (node (ref "C8") (pin "2") (pinfunction "2_2") (pintype "passive"))
      (node (ref "IC2") (pin "C2") (pinfunction "VDD_C2") (pintype "bidirectional"))
      (node (ref "IC3") (pin "10") (pinfunction "CSB_10") (pintype "bidirectional"))
      (node (ref "IC3") (pin "3") (pinfunction "VDDIO_3") (pintype "bidirectional"))
      (node (ref "IC3") (pin "7") (pinfunction "VDD_7") (pintype "bidirectional"))
      (node (ref "IC9") (pin "E2") (pinfunction "VOUT_1_E2") (pintype "bidirectional"))
      (node (ref "IC9") (pin "E3") (pinfunction "VOUT_2_E3") (pintype "bidirectional"))
      (node (ref "J2") (pin "1") (pinfunction "1_1") (pintype "bidirectional"))
      (node (ref "Q1") (pin "2") (pinfunction "S_2") (pintype "bidirectional"))
      (node (ref "R17") (pin "1") (pinfunction "1_1") (pintype "bidirectional"))
      (node (ref "R18") (pin "1") (pinfunction "1_1") (pintype "bidirectional"))
      (node (ref "R5") (pin "2") (pinfunction "2_2") (pintype "bidirectional"))
      (node (ref "R7") (pin "2") (pinfunction "2_2") (pintype "bidirectional"))
      (node (ref "R8") (pin "1") (pinfunction "1_1") (pintype "bidirectional"))
      (node (ref "R_PWR_EPD") (pin "2") (pinfunction "2_2") (pintype "bidirectional"))
      (node (ref "TP_3.3V") (pin "TP") (pinfunction "TP_TP") (pintype "input"))
      (node (ref "TP_3V3") (pin "TP") (pinfunction "TP_TP") (pintype "input"))
      (node (ref "U1") (pin "P$A22") (pinfunction "VDD_P$A22") (pintype "power_in"))
      (node (ref "U1") (pin "P$AD14") (pinfunction "VDD_P$AD14") (pintype "power_in"))
      (node (ref "U1") (pin "P$AD23") (pinfunction "VDD_P$AD23") (pintype "power_in"))
      (node (ref "U1") (pin "P$B1") (pinfunction "VDD_P$B1") (pintype "power_in"))
      (node (ref "U1") (pin "P$W1") (pinfunction "VDD_P$W1") (pintype "power_in"))
      (node (ref "U1") (pin "P$Y2") (pinfunction "VDDH_P$Y2") (pintype "power_in"))
    )
    (net (code "2") (name "ALERT") (class "Default")
      (node (ref "U1") (pin "P$J24") (pinfunction "P0.10/NFC2_P$J24") (pintype "bidirectional"))
      (node (ref "U3") (pin "5") (pinfunction "~{ALERT}_5") (pintype "output"))
    )
    (net (code "3") (name "D+") (class "Default")
      (node (ref "D3") (pin "4") (pinfunction "I/O2_2_4") (pintype "bidirectional"))
      (node (ref "U1") (pin "P$AD6") (pinfunction "D+_P$AD6") (pintype "bidirectional"))
    )
    (net (code "4") (name "D-") (class "Default")
      (node (ref "D3") (pin "6") (pinfunction "I/O1_2_6") (pintype "bidirectional"))
      (node (ref "U1") (pin "P$AD4") (pinfunction "D-_P$AD4") (pintype "bidirectional"))
    )
    (net (code "5") (name "DEC1") (class "Default")
      (node (ref "C5") (pin "2") (pinfunction "2_2") (pintype "passive"))
      (node (ref "U1") (pin "P$C1") (pinfunction "DEC1_P$C1") (pintype "power_in"))
    )
    (net (code "6") (name "DN") (class "Default")
      (node (ref "D3") (pin "1") (pinfunction "I/O1_1_1") (pintype "bidirectional"))
      (node (ref "J4") (pin "A7") (pinfunction "DN1_A7") (pintype "bidirectional"))
      (node (ref "J4") (pin "B7") (pinfunction "DN2_B7") (pintype "bidirectional"))
    )
    (net (code "7") (name "DP") (class "Default")
      (node (ref "D3") (pin "3") (pinfunction "I/O2_1_3") (pintype "bidirectional"))
      (node (ref "J4") (pin "A6") (pinfunction "DP1_A6") (pintype "bidirectional"))
      (node (ref "J4") (pin "B6") (pinfunction "DP2_B6") (pintype "bidirectional"))
    )
    (net (code "8") (name "EPD_3V3") (class "Default")
      (node (ref "C1-EP-DR") (pin "1") (pinfunction "1_1") (pintype "passive"))
      (node (ref "EPD_C5") (pin "2") (pinfunction "2_2") (pintype "passive"))
      (node (ref "J1") (pin "15") (pinfunction "15_15") (pintype "bidirectional"))
      (node (ref "J1") (pin "16") (pinfunction "16_16") (pintype "bidirectional"))
      (node (ref "L5") (pin "1") (pinfunction "1_1") (pintype "bidirectional"))
      (node (ref "Q1") (pin "3") (pinfunction "D_3") (pintype "bidirectional"))
    )
    (net (code "9") (name "EPD_BUSY") (class "Default")
      (node (ref "J1") (pin "9") (pinfunction "9_9") (pintype "bidirectional"))
      (node (ref "U1") (pin "P$AD12") (pinfunction "P0.17_P$AD12") (pintype "bidirectional"))
    )
    (net (code "10") (name "EPD_CS") (class "Default")
      (node (ref "J1") (pin "12") (pinfunction "12_12") (pintype "bidirectional"))
      (node (ref "U1") (pin "P$K2") (pinfunction "P0.05/AIN3_P$K2") (pintype "bidirectional"))
    )
    (net (code "11") (name "EPD_DC") (class "Default")
      (node (ref "J1") (pin "11") (pinfunction "11_11") (pintype "bidirectional"))
      (node (ref "U1") (pin "P$AD10") (pinfunction "P0.15_P$AD10") (pintype "bidirectional"))
    )
    (net (code "12") (name "EPD_RST") (class "Default")
      (node (ref "J1") (pin "10") (pinfunction "10_10") (pintype "bidirectional"))
      (node (ref "U1") (pin "P$AC11") (pinfunction "P0.16_P$AC11") (pintype "bidirectional"))
    )
    (net (code "13") (name "GDR") (class "Default")
      (node (ref "J1") (pin "2") (pinfunction "2_2") (pintype "bidirectional"))
      (node (ref "Q3") (pin "1") (pinfunction "G_1") (pintype "bidirectional"))
      (node (ref "R2_EP_DR1") (pin "2") (pinfunction "2_2") (pintype "bidirectional"))
    )
    (net (code "14") (name "GND") (class "Default")
      (node (ref "C1-EP-DR") (pin "2") (pinfunction "2_2") (pintype "passive"))
      (node (ref "C10") (pin "1") (pinfunction "1_1") (pintype "passive"))
      (node (ref "C11") (pin "1") (pinfunction "1_1") (pintype "passive"))
      (node (ref "C12") (pin "1") (pinfunction "1_1") (pintype "passive"))
      (node (ref "C13") (pin "2") (pinfunction "2_2") (pintype "passive"))
      (node (ref "C14") (pin "2") (pinfunction "2_2") (pintype "passive"))
      (node (ref "C17") (pin "2") (pinfunction "2_2") (pintype "passive"))
      (node (ref "C18") (pin "2") (pinfunction "2_2") (pintype "passive"))
      (node (ref "C19") (pin "2") (pinfunction "2_2") (pintype "passive"))
      (node (ref "C20") (pin "2") (pinfunction "2_2") (pintype "passive"))
      (node (ref "C21") (pin "2") (pinfunction "2_2") (pintype "passive"))
      (node (ref "C22") (pin "1") (pinfunction "1_1") (pintype "passive"))
      (node (ref "C23") (pin "2") (pinfunction "2_2") (pintype "passive"))
      (node (ref "C24") (pin "1") (pinfunction "1_1") (pintype "passive"))
      (node (ref "C25") (pin "2") (pinfunction "2_2") (pintype "passive"))
      (node (ref "C27") (pin "1") (pinfunction "1_1") (pintype "passive"))
      (node (ref "C29") (pin "1") (pinfunction "1_1") (pintype "passive"))
      (node (ref "C3") (pin "1") (pinfunction "1_1") (pintype "passive"))
      (node (ref "C30") (pin "1") (pinfunction "1_1") (pintype "passive"))
      (node (ref "C31") (pin "2") (pinfunction "2_2") (pintype "passive"))
      (node (ref "C32") (pin "1") (pinfunction "1_1") (pintype "passive"))
      (node (ref "C33") (pin "2") (pinfunction "2_2") (pintype "passive"))
      (node (ref "C34") (pin "1") (pinfunction "1_1") (pintype "passive"))
      (node (ref "C37") (pin "2") (pinfunction "2_2") (pintype "passive"))
      (node (ref "C38") (pin "2") (pinfunction "2_2") (pintype "passive"))
      (node (ref "C39") (pin "2") (pinfunction "2_2") (pintype "passive"))
      (node (ref "C4") (pin "1") (pinfunction "1_1") (pintype "passive"))
      (node (ref "C42") (pin "1") (pinfunction "1_1") (pintype "passive"))
      (node (ref "C43") (pin "2") (pinfunction "2_2") (pintype "passive"))
      (node (ref "C5") (pin "1") (pinfunction "1_1") (pintype "passive"))
      (node (ref "C6") (pin "2") (pinfunction "2_2") (pintype "passive"))
      (node (ref "C7") (pin "1") (pinfunction "1_1") (pintype "passive"))
      (node (ref "C8") (pin "1") (pinfunction "1_1") (pintype "passive"))
      (node (ref "C9") (pin "1") (pinfunction "1_1") (pintype "passive"))
      (node (ref "D3") (pin "2") (pinfunction "GND_2") (pintype "bidirectional"))
      (node (ref "D4") (pin "1") (pinfunction "K_1") (pintype "bidirectional"))
      (node (ref "EPD_C1") (pin "1") (pinfunction "1_1") (pintype "passive"))
      (node (ref "EPD_C10") (pin "1") (pinfunction "1_1") (pintype "passive"))
      (node (ref "EPD_C11") (pin "1") (pinfunction "1_1") (pintype "passive"))
      (node (ref "EPD_C12") (pin "1") (pinfunction "1_1") (pintype "passive"))
      (node (ref "EPD_C2") (pin "1") (pinfunction "1_1") (pintype "passive"))
      (node (ref "EPD_C5") (pin "1") (pinfunction "1_1") (pintype "passive"))
      (node (ref "EPD_C6") (pin "1") (pinfunction "1_1") (pintype "passive"))
      (node (ref "EPD_C7") (pin "1") (pinfunction "1_1") (pintype "passive"))
      (node (ref "EPD_C8") (pin "1") (pinfunction "1_1") (pintype "passive"))
      (node (ref "EPD_C9") (pin "1") (pinfunction "1_1") (pintype "passive"))
      (node (ref "IC1") (pin "D2") (pinfunction "GND_D2") (pintype "bidirectional"))
      (node (ref "IC2") (pin "B1") (pinfunction "IN/TRIG_B1") (pintype "bidirectional"))
      (node (ref "IC2") (pin "B3") (pinfunction "GND_B3") (pintype "bidirectional"))
      (node (ref "IC3") (pin "8") (pinfunction "GNDIO_8") (pintype "bidirectional"))
      (node (ref "IC3") (pin "9") (pinfunction "GND_9") (pintype "bidirectional"))
      (node (ref "IC9") (pin "B1") (pinfunction "VSEL_B1") (pintype "bidirectional"))
      (node (ref "IC9") (pin "C2") (pinfunction "PGND_1_C2") (pintype "bidirectional"))
      (node (ref "IC9") (pin "C3") (pinfunction "PGND_2_C3") (pintype "bidirectional"))
      (node (ref "J1") (pin "17") (pinfunction "17_17") (pintype "bidirectional"))
      (node (ref "J1") (pin "8") (pinfunction "8_8") (pintype "bidirectional"))
      (node (ref "J1") (pin "MP1") (pinfunction "MP1_MP1") (pintype "bidirectional"))
      (node (ref "J1") (pin "MP2") (pinfunction "MP2_MP2") (pintype "bidirectional"))
      (node (ref "J2") (pin "3") (pinfunction "3_3") (pintype "bidirectional"))
      (node (ref "J2") (pin "5") (pinfunction "5_5") (pintype "bidirectional"))
      (node (ref "J4") (pin "A12_B1") (pinfunction "GND_A12_B1") (pintype "power_in"))
      (node (ref "J4") (pin "A1_B12") (pinfunction "GND_A1_B12") (pintype "power_in"))
      (node (ref "J4") (pin "SH1") (pinfunction "SHIELD_SH1") (pintype "passive"))
      (node (ref "J4") (pin "SH2") (pinfunction "SHIELD_SH2") (pintype "passive"))
      (node (ref "J4") (pin "SH3") (pinfunction "SHIELD_SH3") (pintype "passive"))
      (node (ref "J4") (pin "SH4") (pinfunction "SHIELD_SH4") (pintype "passive"))
      (node (ref "R1") (pin "2") (pinfunction "2_2") (pintype "bidirectional"))
      (node (ref "R1_USB") (pin "1") (pinfunction "1_1") (pintype "bidirectional"))
      (node (ref "R2_EP_DR1") (pin "1") (pinfunction "1_1") (pintype "bidirectional"))
      (node (ref "R2_USB") (pin "2") (pinfunction "2_2") (pintype "bidirectional"))
      (node (ref "R9") (pin "1") (pinfunction "1_1") (pintype "bidirectional"))
      (node (ref "R_TYPE_SEL") (pin "1") (pinfunction "1_1") (pintype "bidirectional"))
      (node (ref "SJ1") (pin "1") (pinfunction "1_1") (pintype "passive"))
      (node (ref "SW_DN") (pin "1") (pinfunction "1_1") (pintype "passive"))
      (node (ref "SW_ENT") (pin "1") (pinfunction "1_1") (pintype "passive"))
      (node (ref "SW_UP") (pin "1") (pinfunction "1_1") (pintype "passive"))
      (node (ref "TP_BAT_GND") (pin "TP") (pinfunction "TP_TP") (pintype "input"))
      (node (ref "TP_GND") (pin "TP") (pinfunction "TP_TP") (pintype "input"))
      (node (ref "U1") (pin "P$74") (pinfunction "VSS_PAD_P$74") (pintype "bidirectional"))
      (node (ref "U1") (pin "P$75") (pinfunction "VSS_PAD_P$75") (pintype "bidirectional"))
      (node (ref "U1") (pin "P$76") (pinfunction "VSS_PAD_P$76") (pintype "bidirectional"))
      (node (ref "U1") (pin "P$77") (pinfunction "VSS_PAD_P$77") (pintype "bidirectional"))
      (node (ref "U1") (pin "P$78") (pinfunction "VSS_PAD_P$78") (pintype "bidirectional"))
      (node (ref "U1") (pin "P$79") (pinfunction "VSS_PAD_P$79") (pintype "bidirectional"))
      (node (ref "U1") (pin "P$80") (pinfunction "VSS_PAD_P$80") (pintype "bidirectional"))
      (node (ref "U1") (pin "P$81") (pinfunction "VSS_PAD_P$81") (pintype "bidirectional"))
      (node (ref "U1") (pin "P$82") (pinfunction "VSS_PAD_P$82") (pintype "bidirectional"))
      (node (ref "U1") (pin "P$83") (pinfunction "VSS_PAD_P$83") (pintype "bidirectional"))
      (node (ref "U1") (pin "P$84") (pinfunction "VSS_PAD_P$84") (pintype "bidirectional"))
      (node (ref "U1") (pin "P$85") (pinfunction "VSS_PAD_P$85") (pintype "bidirectional"))
      (node (ref "U1") (pin "P$86") (pinfunction "VSS_PAD_P$86") (pintype "bidirectional"))
      (node (ref "U1") (pin "P$87") (pinfunction "VSS_PAD_P$87") (pintype "bidirectional"))
      (node (ref "U1") (pin "P$88") (pinfunction "VSS_PAD_P$88") (pintype "bidirectional"))
      (node (ref "U1") (pin "P$89") (pinfunction "VSS_PAD_P$89") (pintype "bidirectional"))
      (node (ref "U1") (pin "P$90") (pinfunction "VSS_PAD_P$90") (pintype "bidirectional"))
      (node (ref "U1") (pin "P$F23") (pinfunction "VSS_PA_P$F23") (pintype "bidirectional"))
      (node (ref "U3") (pin "1") (pinfunction "CTG_1") (pintype "power_in"))
      (node (ref "U3") (pin "4") (pinfunction "GND_4") (pintype "power_in"))
      (node (ref "U3") (pin "6") (pinfunction "QSTRT_6") (pintype "input"))
      (node (ref "U3") (pin "9") (pinfunction "EP_9") (pintype "power_in"))
    )
    (net (code "15") (name "HAPTIC_EN") (class "Default")
      (node (ref "IC2") (pin "A1") (pinfunction "EN_A1") (pintype "bidirectional"))
      (node (ref "U1") (pin "P$U1") (pinfunction "P0.12_P$U1") (pintype "bidirectional"))
    )
    (net (code "16") (name "IMU_INT1") (class "Default")
      (node (ref "IC3") (pin "5") (pinfunction "INT1_5") (pintype "bidirectional"))
      (node (ref "U1") (pin "P$N1") (pinfunction "P0.08_P$N1") (pintype "bidirectional"))
    )
    (net (code "17") (name "IMU_INT2") (class "Default")
      (node (ref "IC3") (pin "6") (pinfunction "INT2_6") (pintype "bidirectional"))
      (node (ref "U1") (pin "P$P2") (pinfunction "P1.08_P$P2") (pintype "bidirectional"))
    )
    (net (code "18") (name "LX1") (class "Default")
      (node (ref "IC9") (pin "B2") (pinfunction "SW1_1_B2") (pintype "bidirectional"))
      (node (ref "IC9") (pin "B3") (pinfunction "SW1_2_B3") (pintype "bidirectional"))
      (node (ref "L7") (pin "1") (pinfunction "1_1") (pintype "bidirectional"))
    )
    (net (code "19") (name "LX2") (class "Default")
      (node (ref "IC9") (pin "D2") (pinfunction "SW2_1_D2") (pintype "bidirectional"))
      (node (ref "IC9") (pin "D3") (pinfunction "SW2_2_D3") (pintype "bidirectional"))
      (node (ref "L7") (pin "2") (pinfunction "2_2") (pintype "bidirectional"))
    )
    (net (code "20") (name "MOSI") (class "Default")
      (node (ref "J1") (pin "14") (pinfunction "14_14") (pintype "bidirectional"))
      (node (ref "U1") (pin "P$B13") (pinfunction "P0.03/AIN1_P$B13") (pintype "bidirectional"))
    )
    (net (code "21") (name "Net-(ANT1-FEED)") (class "Default")
      (node (ref "ANT1") (pin "1") (pinfunction "FEED_1") (pintype "input"))
      (node (ref "C22") (pin "2") (pinfunction "2_2") (pintype "passive"))
      (node (ref "C4") (pin "2") (pinfunction "2_2") (pintype "passive"))
      (node (ref "L1") (pin "2") (pinfunction "2_2") (pintype "bidirectional"))
    )
    (net (code "22") (name "Net-(C1-Pad2)") (class "Default")
      (node (ref "C1") (pin "2") (pinfunction "2_2") (pintype "passive"))
      (node (ref "X1") (pin "2") (pinfunction "2_2") (pintype "passive"))
    )
    (net (code "23") (name "Net-(C2-Pad1)") (class "Default")
      (node (ref "C2") (pin "1") (pinfunction "1_1") (pintype "passive"))
      (node (ref "X1") (pin "4") (pinfunction "4_4") (pintype "passive"))
    )
    (net (code "24") (name "Net-(D2-K)") (class "Default")
      (node (ref "C2-EP-DR") (pin "1") (pinfunction "1_1") (pintype "passive"))
      (node (ref "D2") (pin "1") (pinfunction "K_1") (pintype "bidirectional"))
      (node (ref "D4") (pin "2") (pinfunction "A_2") (pintype "bidirectional"))
    )
    (net (code "25") (name "Net-(D5-A)") (class "Default")
      (node (ref "C2-EP-DR") (pin "2") (pinfunction "2_2") (pintype "passive"))
      (node (ref "D5") (pin "2") (pinfunction "A_2") (pintype "bidirectional"))
      (node (ref "L5") (pin "2") (pinfunction "2_2") (pintype "bidirectional"))
      (node (ref "Q3") (pin "3") (pinfunction "D_3") (pintype "bidirectional"))
    )
    (net (code "26") (name "Net-(EPD_C1-Pad2)") (class "Default")
      (node (ref "EPD_C1") (pin "2") (pinfunction "2_2") (pintype "passive"))
      (node (ref "J1") (pin "5") (pinfunction "5_5") (pintype "bidirectional"))
    )
    (net (code "27") (name "Net-(EPD_C2-Pad2)") (class "Default")
      (node (ref "EPD_C2") (pin "2") (pinfunction "2_2") (pintype "passive"))
      (node (ref "J1") (pin "4") (pinfunction "4_4") (pintype "bidirectional"))
    )
    (net (code "28") (name "Net-(EPD_C6-Pad2)") (class "Default")
      (node (ref "EPD_C6") (pin "2") (pinfunction "2_2") (pintype "passive"))
      (node (ref "J1") (pin "18") (pinfunction "18_18") (pintype "bidirectional"))
    )
    (net (code "29") (name "Net-(EPD_C7-Pad2)") (class "Default")
      (node (ref "EPD_C7") (pin "2") (pinfunction "2_2") (pintype "passive"))
      (node (ref "J1") (pin "19") (pinfunction "19_19") (pintype "bidirectional"))
    )
    (net (code "30") (name "Net-(EPD_C8-Pad2)") (class "Default")
      (node (ref "EPD_C8") (pin "2") (pinfunction "2_2") (pintype "passive"))
      (node (ref "J1") (pin "20") (pinfunction "20_20") (pintype "bidirectional"))
    )
    (net (code "31") (name "Net-(EPD_C10-Pad2)") (class "Default")
      (node (ref "EPD_C10") (pin "2") (pinfunction "2_2") (pintype "passive"))
      (node (ref "J1") (pin "22") (pinfunction "22_22") (pintype "bidirectional"))
    )
    (net (code "32") (name "Net-(EPD_C12-Pad2)") (class "Default")
      (node (ref "EPD_C12") (pin "2") (pinfunction "2_2") (pintype "passive"))
      (node (ref "J1") (pin "24") (pinfunction "24_24") (pintype "bidirectional"))
    )
    (net (code "33") (name "Net-(IC1-TS{slash}MR)") (class "Default")
      (node (ref "IC1") (pin "D1") (pinfunction "TS/MR_D1") (pintype "bidirectional"))
      (node (ref "R9") (pin "2") (pinfunction "2_2") (pintype "bidirectional"))
    )
    (net (code "34") (name "Net-(IC2-REG)") (class "Default")
      (node (ref "C32") (pin "2") (pinfunction "2_2") (pintype "passive"))
      (node (ref "IC2") (pin "A2") (pinfunction "REG_A2") (pintype "bidirectional"))
    )
    (net (code "35") (name "Net-(IC3-SDO)") (class "Default")
      (node (ref "IC3") (pin "1") (pinfunction "SDO_1") (pintype "bidirectional"))
      (node (ref "R1") (pin "1") (pinfunction "1_1") (pintype "bidirectional"))
    )
    (net (code "36") (name "Net-(IC9-SCL)") (class "Default")
      (node (ref "IC9") (pin "D1") (pinfunction "SCL_D1") (pintype "bidirectional"))
      (node (ref "R4") (pin "2") (pinfunction "2_2") (pintype "bidirectional"))
    )
    (net (code "37") (name "Net-(IC9-SDA)") (class "Default")
      (node (ref "IC9") (pin "E1") (pinfunction "SDA_E1") (pintype "bidirectional"))
      (node (ref "R2") (pin "2") (pinfunction "2_2") (pintype "bidirectional"))
    )
    (net (code "38") (name "Net-(J4-CC1)") (class "Default")
      (node (ref "J4") (pin "A5") (pinfunction "CC1_A5") (pintype "bidirectional"))
      (node (ref "R1_USB") (pin "2") (pinfunction "2_2") (pintype "bidirectional"))
    )
    (net (code "39") (name "Net-(J4-CC2)") (class "Default")
      (node (ref "J4") (pin "B5") (pinfunction "CC2_B5") (pintype "bidirectional"))
      (node (ref "R2_USB") (pin "1") (pinfunction "1_1") (pintype "bidirectional"))
    )
    (net (code "40") (name "Net-(L2-Pad2)") (class "Default")
      (node (ref "L2") (pin "2") (pinfunction "2_2") (pintype "bidirectional"))
      (node (ref "L3") (pin "1") (pinfunction "1_1") (pintype "bidirectional"))
    )
    (net (code "41") (name "Net-(R1_EP_DR-Pad1)") (class "Default")
      (node (ref "R1_EP_DR") (pin "1") (pinfunction "1_1") (pintype "bidirectional"))
      (node (ref "R_TYPE_SEL") (pin "2") (pinfunction "2_2") (pintype "bidirectional"))
      (node (ref "SJ1") (pin "2") (pinfunction "2_2") (pintype "passive"))
    )
    (net (code "42") (name "Net-(U1-ANT)") (class "Default")
      (node (ref "C3") (pin "2") (pinfunction "2_2") (pintype "passive"))
      (node (ref "L1") (pin "1") (pinfunction "1_1") (pintype "bidirectional"))
      (node (ref "U1") (pin "P$H23") (pinfunction "ANT_P$H23") (pintype "bidirectional"))
    )
    (net (code "43") (name "Net-(U1-DCC)") (class "Default")
      (node (ref "L2") (pin "1") (pinfunction "1_1") (pintype "bidirectional"))
      (node (ref "U1") (pin "P$B3") (pinfunction "DCC_P$B3") (pintype "output"))
    )
    (net (code "44") (name "Net-(U1-DEC2)") (class "Default")
      (node (ref "C13") (pin "1") (pinfunction "1_1") (pintype "passive"))
      (node (ref "U1") (pin "P$A18") (pinfunction "DEC2_P$A18") (pintype "bidirectional"))
    )
    (net (code "45") (name "Net-(U1-DEC3)") (class "Default")
      (node (ref "C11") (pin "2") (pinfunction "2_2") (pintype "passive"))
      (node (ref "U1") (pin "P$D23") (pinfunction "DEC3_P$D23") (pintype "bidirectional"))
    )
    (net (code "46") (name "Net-(U1-DEC3V3)") (class "Default")
      (node (ref "C20") (pin "1") (pinfunction "1_1") (pintype "passive"))
      (node (ref "U1") (pin "P$AC5") (pinfunction "DEC3V3_P$AC5") (pintype "bidirectional"))
    )
    (net (code "47") (name "Net-(U1-DEC4)") (class "Default")
      (node (ref "C10") (pin "2") (pinfunction "2_2") (pintype "passive"))
      (node (ref "C15") (pin "2") (pinfunction "2_2") (pintype "passive"))
      (node (ref "C16") (pin "1") (pinfunction "1_1") (pintype "passive"))
      (node (ref "L3") (pin "2") (pinfunction "2_2") (pintype "bidirectional"))
      (node (ref "U1") (pin "P$B5") (pinfunction "DEC4_P$B5") (pintype "power_in"))
      (node (ref "U1") (pin "P$E24") (pinfunction "DEC6_P$E24") (pintype "bidirectional"))
    )
    (net (code "48") (name "Net-(U1-DEC5)") (class "Default")
      (node (ref "C9") (pin "2") (pinfunction "2_2") (pintype "passive"))
      (node (ref "U1") (pin "P$N24") (pinfunction "DEC5_P$N24") (pintype "bidirectional"))
    )
    (net (code "49") (name "Net-(U1-VSS)") (class "Default")
      (node (ref "C15") (pin "1") (pinfunction "1_1") (pintype "passive"))
      (node (ref "C16") (pin "2") (pinfunction "2_2") (pintype "passive"))
      (node (ref "U1") (pin "P$B7") (pinfunction "VSS_P$B7") (pintype "power_in"))
    )
    (net (code "50") (name "Net-(U1-XC1)") (class "Default")
      (node (ref "C1") (pin "1") (pinfunction "1_1") (pintype "passive"))
      (node (ref "U1") (pin "P$B24") (pinfunction "XC1_P$B24") (pintype "input"))
      (node (ref "X1") (pin "1") (pinfunction "1_1") (pintype "passive"))
    )
    (net (code "51") (name "Net-(U1-XC2)") (class "Default")
      (node (ref "C2") (pin "2") (pinfunction "2_2") (pintype "passive"))
      (node (ref "U1") (pin "P$A23") (pinfunction "XC2_P$A23") (pintype "output"))
      (node (ref "X1") (pin "3") (pinfunction "3_3") (pintype "passive"))
    )
    (net (code "52") (name "OUT+") (class "Default")
      (node (ref "IC2") (pin "A3") (pinfunction "OUT+_A3") (pintype "bidirectional"))
      (node (ref "TP1") (pin "TP") (pinfunction "TP_TP") (pintype "input"))
    )
    (net (code "53") (name "OUT-") (class "Default")
      (node (ref "IC2") (pin "C3") (pinfunction "OUT-_C3") (pintype "bidirectional"))
      (node (ref "TP2") (pin "TP") (pinfunction "TP_TP") (pintype "input"))
    )
    (net (code "54") (name "P0.00{slash}XL1") (class "Default")
      (node (ref "C17") (pin "1") (pinfunction "1_1") (pintype "passive"))
      (node (ref "U1") (pin "P$D2") (pinfunction "P0.00/XL1_P$D2") (pintype "bidirectional"))
      (node (ref "X2") (pin "2") (pinfunction "2_2") (pintype "passive"))
    )
    (net (code "55") (name "P0.00{slash}XL2") (class "Default")
      (node (ref "C18") (pin "1") (pinfunction "1_1") (pintype "passive"))
      (node (ref "U1") (pin "P$F2") (pinfunction "P0.01/XL2_P$F2") (pintype "bidirectional"))
      (node (ref "X2") (pin "1") (pinfunction "1_1") (pintype "passive"))
    )
    (net (code "56") (name "P0.04") (class "Default")
      (node (ref "U1") (pin "P$J1") (pinfunction "P0.04/AIN2_P$J1") (pintype "bidirectional"))
    )
    (net (code "57") (name "P0.09") (class "Default")
      (node (ref "U1") (pin "P$L24") (pinfunction "P0.09/NFC1_P$L24") (pintype "bidirectional"))
    )
    (net (code "58") (name "P0.13") (class "Default")
      (node (ref "C30") (pin "2") (pinfunction "2_2") (pintype "passive"))
      (node (ref "R5") (pin "1") (pinfunction "1_1") (pintype "bidirectional"))
      (node (ref "SW_UP") (pin "2") (pinfunction "2_2") (pintype "passive"))
      (node (ref "U1") (pin "P$AD8") (pinfunction "P0.13_P$AD8") (pintype "bidirectional"))
    )
    (net (code "59") (name "P0.14") (class "Default")
      (node (ref "C31") (pin "1") (pinfunction "1_1") (pintype "passive"))
      (node (ref "R8") (pin "2") (pinfunction "2_2") (pintype "bidirectional"))
      (node (ref "SW_ENT") (pin "2") (pinfunction "2_2") (pintype "passive"))
      (node (ref "U1") (pin "P$AC9") (pinfunction "P0.14_P$AC9") (pintype "bidirectional"))
    )
    (net (code "60") (name "P0.19") (class "Default")
      (node (ref "U1") (pin "P$AC15") (pinfunction "P0.19_P$AC15") (pintype "bidirectional"))
    )
    (net (code "61") (name "P0.20") (class "Default")
      (node (ref "U1") (pin "P$AD16") (pinfunction "P0.20_P$AD16") (pintype "bidirectional"))
    )
    (net (code "62") (name "P0.21") (class "Default")
      (node (ref "U1") (pin "P$AC17") (pinfunction "P0.21_P$AC17") (pintype "bidirectional"))
    )
    (net (code "63") (name "P0.22") (class "Default")
      (node (ref "U1") (pin "P$AD18") (pinfunction "P0.22_P$AD18") (pintype "bidirectional"))
    )
    (net (code "64") (name "P0.23") (class "Default")
      (node (ref "U1") (pin "P$AC19") (pinfunction "P0.23_P$AC19") (pintype "bidirectional"))
    )
    (net (code "65") (name "P0.24") (class "Default")
      (node (ref "U1") (pin "P$AD20") (pinfunction "P0.24_P$AD20") (pintype "bidirectional"))
    )
    (net (code "66") (name "P0.25") (class "Default")
      (node (ref "U1") (pin "P$AC21") (pinfunction "P0.25_P$AC21") (pintype "bidirectional"))
    )
    (net (code "67") (name "P0.26") (class "Default")
      (node (ref "U1") (pin "P$G1") (pinfunction "P0.26_P$G1") (pintype "bidirectional"))
    )
    (net (code "68") (name "P0.27") (class "Default")
      (node (ref "U1") (pin "P$H2") (pinfunction "P0.27_P$H2") (pintype "bidirectional"))
    )
    (net (code "69") (name "P0.28") (class "Default")
      (node (ref "U1") (pin "P$B11") (pinfunction "P0.28/AIN4_P$B11") (pintype "bidirectional"))
    )
    (net (code "70") (name "P0.29") (class "Default")
      (node (ref "U1") (pin "P$A10") (pinfunction "P0.29/AIN5_P$A10") (pintype "bidirectional"))
    )
    (net (code "71") (name "P0.30") (class "Default")
      (node (ref "U1") (pin "P$B9") (pinfunction "P0.30/AIN6_P$B9") (pintype "bidirectional"))
    )
    (net (code "72") (name "P0.31") (class "Default")
      (node (ref "U1") (pin "P$A8") (pinfunction "P0.31/AIN7_P$A8") (pintype "bidirectional"))
    )
    (net (code "73") (name "P1.01") (class "Default")
      (node (ref "Q1") (pin "1") (pinfunction "G_1") (pintype "bidirectional"))
      (node (ref "R_PWR_EPD") (pin "1") (pinfunction "1_1") (pintype "bidirectional"))
      (node (ref "U1") (pin "P$Y23") (pinfunction "P1.01_P$Y23") (pintype "bidirectional"))
    )
    (net (code "74") (name "P1.02") (class "Default")
      (node (ref "C29") (pin "2") (pinfunction "2_2") (pintype "passive"))
      (node (ref "R7") (pin "1") (pinfunction "1_1") (pintype "bidirectional"))
      (node (ref "SW_DN") (pin "2") (pinfunction "2_2") (pintype "passive"))
      (node (ref "U1") (pin "P$W24") (pinfunction "P1.02_P$W24") (pintype "bidirectional"))
    )
    (net (code "75") (name "P1.03") (class "Default")
      (node (ref "U1") (pin "P$V23") (pinfunction "P1.03_P$V23") (pintype "bidirectional"))
    )
    (net (code "76") (name "P1.04") (class "Default")
      (node (ref "U1") (pin "P$U24") (pinfunction "P1.04_P$U24") (pintype "bidirectional"))
    )
    (net (code "77") (name "P1.05") (class "Default")
      (node (ref "U1") (pin "P$T23") (pinfunction "P1.05_P$T23") (pintype "bidirectional"))
    )
    (net (code "78") (name "P1.06") (class "Default")
      (node (ref "U1") (pin "P$R24") (pinfunction "P1.06_P$R24") (pintype "bidirectional"))
    )
    (net (code "79") (name "P1.07") (class "Default")
      (node (ref "U1") (pin "P$P23") (pinfunction "P1.07_P$P23") (pintype "bidirectional"))
    )
    (net (code "80") (name "P1.09") (class "Default")
      (node (ref "U1") (pin "P$R1") (pinfunction "P1.09_P$R1") (pintype "bidirectional"))
    )
    (net (code "81") (name "P1.10") (class "Default")
      (node (ref "U1") (pin "P$A20") (pinfunction "P1.10_P$A20") (pintype "bidirectional"))
    )
    (net (code "82") (name "P1.11") (class "Default")
      (node (ref "U1") (pin "P$B19") (pinfunction "P1.11_P$B19") (pintype "bidirectional"))
    )
    (net (code "83") (name "P1.12") (class "Default")
      (node (ref "U1") (pin "P$B17") (pinfunction "P1.12_P$B17") (pintype "bidirectional"))
    )
    (net (code "84") (name "P1.13") (class "Default")
      (node (ref "U1") (pin "P$A16") (pinfunction "P1.13_P$A16") (pintype "bidirectional"))
    )
    (net (code "85") (name "P1.14") (class "Default")
      (node (ref "U1") (pin "P$B15") (pinfunction "P1.14_P$B15") (pintype "bidirectional"))
    )
    (net (code "86") (name "P1.15") (class "Default")
      (node (ref "U1") (pin "P$A14") (pinfunction "P1.15_P$A14") (pintype "bidirectional"))
    )
    (net (code "87") (name "PMIC_INT") (class "Default")
      (node (ref "IC1") (pin "A1") (pinfunction "~{INT}_A1") (pintype "bidirectional"))
      (node (ref "U1") (pin "P$T2") (pinfunction "P0.11_P$T2") (pintype "bidirectional"))
    )
    (net (code "88") (name "PREVGH") (class "Default")
      (node (ref "D5") (pin "1") (pinfunction "K_1") (pintype "bidirectional"))
      (node (ref "EPD_C9") (pin "2") (pinfunction "2_2") (pintype "passive"))
      (node (ref "J1") (pin "21") (pinfunction "21_21") (pintype "bidirectional"))
    )
    (net (code "89") (name "PREVGL") (class "Default")
      (node (ref "D2") (pin "2") (pinfunction "A_2") (pintype "bidirectional"))
      (node (ref "EPD_C11") (pin "2") (pinfunction "2_2") (pintype "passive"))
      (node (ref "J1") (pin "23") (pinfunction "23_23") (pintype "bidirectional"))
    )
    (net (code "90") (name "RESET") (class "Default")
      (node (ref "J1") (pin "3") (pinfunction "3_3") (pintype "bidirectional"))
      (node (ref "J2") (pin "6") (pinfunction "6_6") (pintype "bidirectional"))
      (node (ref "Q3") (pin "2") (pinfunction "S_2") (pintype "bidirectional"))
      (node (ref "R1_EP_DR") (pin "2") (pinfunction "2_2") (pintype "bidirectional"))
      (node (ref "TP_RESET") (pin "TP") (pinfunction "TP_TP") (pintype "input"))
      (node (ref "U1") (pin "P$AC13") (pinfunction "P0.18/RESET_P$AC13") (pintype "bidirectional"))
    )
    (net (code "91") (name "SCK") (class "Default")
      (node (ref "J1") (pin "13") (pinfunction "13_13") (pintype "bidirectional"))
      (node (ref "U1") (pin "P$A12") (pinfunction "P0.02/AIN0_P$A12") (pintype "bidirectional"))
    )
    (net (code "92") (name "SCL") (class "Default")
      (node (ref "IC1") (pin "B1") (pinfunction "SCL_B1") (pintype "bidirectional"))
      (node (ref "IC2") (pin "C1") (pinfunction "SCL_C1") (pintype "bidirectional"))
      (node (ref "IC3") (pin "12") (pinfunction "SCX_12") (pintype "bidirectional"))
      (node (ref "R17") (pin "2") (pinfunction "2_2") (pintype "bidirectional"))
      (node (ref "R4") (pin "1") (pinfunction "1_1") (pintype "bidirectional"))
      (node (ref "TP_SCL") (pin "TP") (pinfunction "TP_TP") (pintype "input"))
      (node (ref "U1") (pin "P$M2") (pinfunction "P0.07_P$M2") (pintype "bidirectional"))
      (node (ref "U3") (pin "7") (pinfunction "SCL_7") (pintype "input"))
    )
    (net (code "93") (name "SDA") (class "Default")
      (node (ref "IC1") (pin "C1") (pinfunction "SDA_C1") (pintype "bidirectional"))
      (node (ref "IC2") (pin "B2") (pinfunction "SDA_B2") (pintype "bidirectional"))
      (node (ref "IC3") (pin "2") (pinfunction "SDX_2") (pintype "bidirectional"))
      (node (ref "R18") (pin "2") (pinfunction "2_2") (pintype "bidirectional"))
      (node (ref "R2") (pin "1") (pinfunction "1_1") (pintype "bidirectional"))
      (node (ref "TP_SDA") (pin "TP") (pinfunction "TP_TP") (pintype "input"))
      (node (ref "U1") (pin "P$L1") (pinfunction "P0.06_P$L1") (pintype "bidirectional"))
      (node (ref "U3") (pin "8") (pinfunction "SDA_8") (pintype "bidirectional"))
    )
    (net (code "94") (name "SWDCLK") (class "Default")
      (node (ref "J2") (pin "4") (pinfunction "4_4") (pintype "bidirectional"))
      (node (ref "TP_SWDCLK") (pin "TP") (pinfunction "TP_TP") (pintype "input"))
      (node (ref "U1") (pin "P$AA24") (pinfunction "SWDCLK_P$AA24") (pintype "input"))
    )
    (net (code "95") (name "SWDIO") (class "Default")
      (node (ref "J2") (pin "2") (pinfunction "2_2") (pintype "bidirectional"))
      (node (ref "TP_SWDIO") (pin "TP") (pinfunction "TP_TP") (pintype "input"))
      (node (ref "U1") (pin "P$AC24") (pinfunction "SWDIO_P$AC24") (pintype "bidirectional"))
    )
    (net (code "96") (name "SWO") (class "Default")
      (node (ref "TP_SWO") (pin "TP") (pinfunction "TP_TP") (pintype "input"))
      (node (ref "U1") (pin "P$AD22") (pinfunction "P1.00_P$AD22") (pintype "bidirectional"))
    )
    (net (code "97") (name "VBAT") (class "Default")
      (node (ref "C27") (pin "2") (pinfunction "2_2") (pintype "passive"))
      (node (ref "C37") (pin "1") (pinfunction "1_1") (pintype "passive"))
      (node (ref "IC1") (pin "C2") (pinfunction "BAT_C2") (pintype "bidirectional"))
      (node (ref "TP_VBAT") (pin "TP") (pinfunction "TP_TP") (pintype "input"))
      (node (ref "U3") (pin "2") (pinfunction "CELL_2") (pintype "power_in"))
      (node (ref "U3") (pin "3") (pinfunction "VDD_3") (pintype "power_in"))
    )
    (net (code "98") (name "VBUS") (class "Default")
      (node (ref "C21") (pin "1") (pinfunction "1_1") (pintype "passive"))
      (node (ref "C38") (pin "1") (pinfunction "1_1") (pintype "passive"))
      (node (ref "C42") (pin "2") (pinfunction "2_2") (pintype "passive"))
      (node (ref "C43") (pin "1") (pinfunction "1_1") (pintype "passive"))
      (node (ref "D3") (pin "5") (pinfunction "VBUS_5") (pintype "bidirectional"))
      (node (ref "IC1") (pin "A2") (pinfunction "IN_A2") (pintype "bidirectional"))
      (node (ref "J4") (pin "A4_B9") (pinfunction "VBUS_A4_B9") (pintype "power_in"))
      (node (ref "J4") (pin "A9_B4") (pinfunction "VBUS_A9_B4") (pintype "power_in"))
      (node (ref "U1") (pin "P$AD2") (pinfunction "VBUS_P$AD2") (pintype "power_in"))
    )
    (net (code "99") (name "VREG") (class "Default")
      (node (ref "C23") (pin "1") (pinfunction "1_1") (pintype "passive"))
      (node (ref "C24") (pin "2") (pinfunction "2_2") (pintype "passive"))
      (node (ref "C39") (pin "1") (pinfunction "1_1") (pintype "passive"))
      (node (ref "IC1") (pin "B2") (pinfunction "SYS_B2") (pintype "bidirectional"))
      (node (ref "IC9") (pin "A1") (pinfunction "EN_A1") (pintype "bidirectional"))
      (node (ref "IC9") (pin "A2") (pinfunction "VIN_1_A2") (pintype "bidirectional"))
      (node (ref "IC9") (pin "A3") (pinfunction "VIN_2_A3") (pintype "bidirectional"))
      (node (ref "TP_VREG") (pin "TP") (pinfunction "TP_TP") (pintype "input"))
    )
    (net (code "100") (name "unconnected-(ANT1-NC-Pad2)") (class "Default")
      (node (ref "ANT1") (pin "2") (pinfunction "NC_2") (pintype "no_connect"))
    )
    (net (code "101") (name "unconnected-(IC3-ASCL-Pad11)") (class "Default")
      (node (ref "IC3") (pin "11") (pinfunction "ASCL_11") (pintype "bidirectional"))
    )
    (net (code "102") (name "unconnected-(IC3-ASDA-Pad4)") (class "Default")
      (node (ref "IC3") (pin "4") (pinfunction "ASDA_4") (pintype "bidirectional"))
    )
    (net (code "103") (name "unconnected-(IC9-AGND-PadC1)") (class "Default")
      (node (ref "IC9") (pin "C1") (pinfunction "AGND_C1") (pintype "bidirectional"))
    )
    (net (code "104") (name "unconnected-(J1-Pad1)") (class "Default")
      (node (ref "J1") (pin "1") (pinfunction "1_1") (pintype "bidirectional"))
    )
    (net (code "105") (name "unconnected-(J1-Pad6)") (class "Default")
      (node (ref "J1") (pin "6") (pinfunction "6_6") (pintype "bidirectional"))
    )
    (net (code "106") (name "unconnected-(J1-Pad7)") (class "Default")
      (node (ref "J1") (pin "7") (pinfunction "7_7") (pintype "bidirectional"))
    )
    (net (code "107") (name "unconnected-(J4-SBU1-PadA8)") (class "Default")
      (node (ref "J4") (pin "A8") (pinfunction "SBU1_A8") (pintype "bidirectional"))
    )
    (net (code "108") (name "unconnected-(J4-SBU2-PadB8)") (class "Default")
      (node (ref "J4") (pin "B8") (pinfunction "SBU2_B8") (pintype "bidirectional"))
    )
    (net (code "109") (name "unconnected-(U1-DCCH-PadP$AB2)") (class "Default")
      (node (ref "U1") (pin "P$AB2") (pinfunction "DCCH_P$AB2") (pintype "bidirectional"))
    )
  )
)
